# fx3.net
KiCad netlist of a schematic drawn in EAGLE
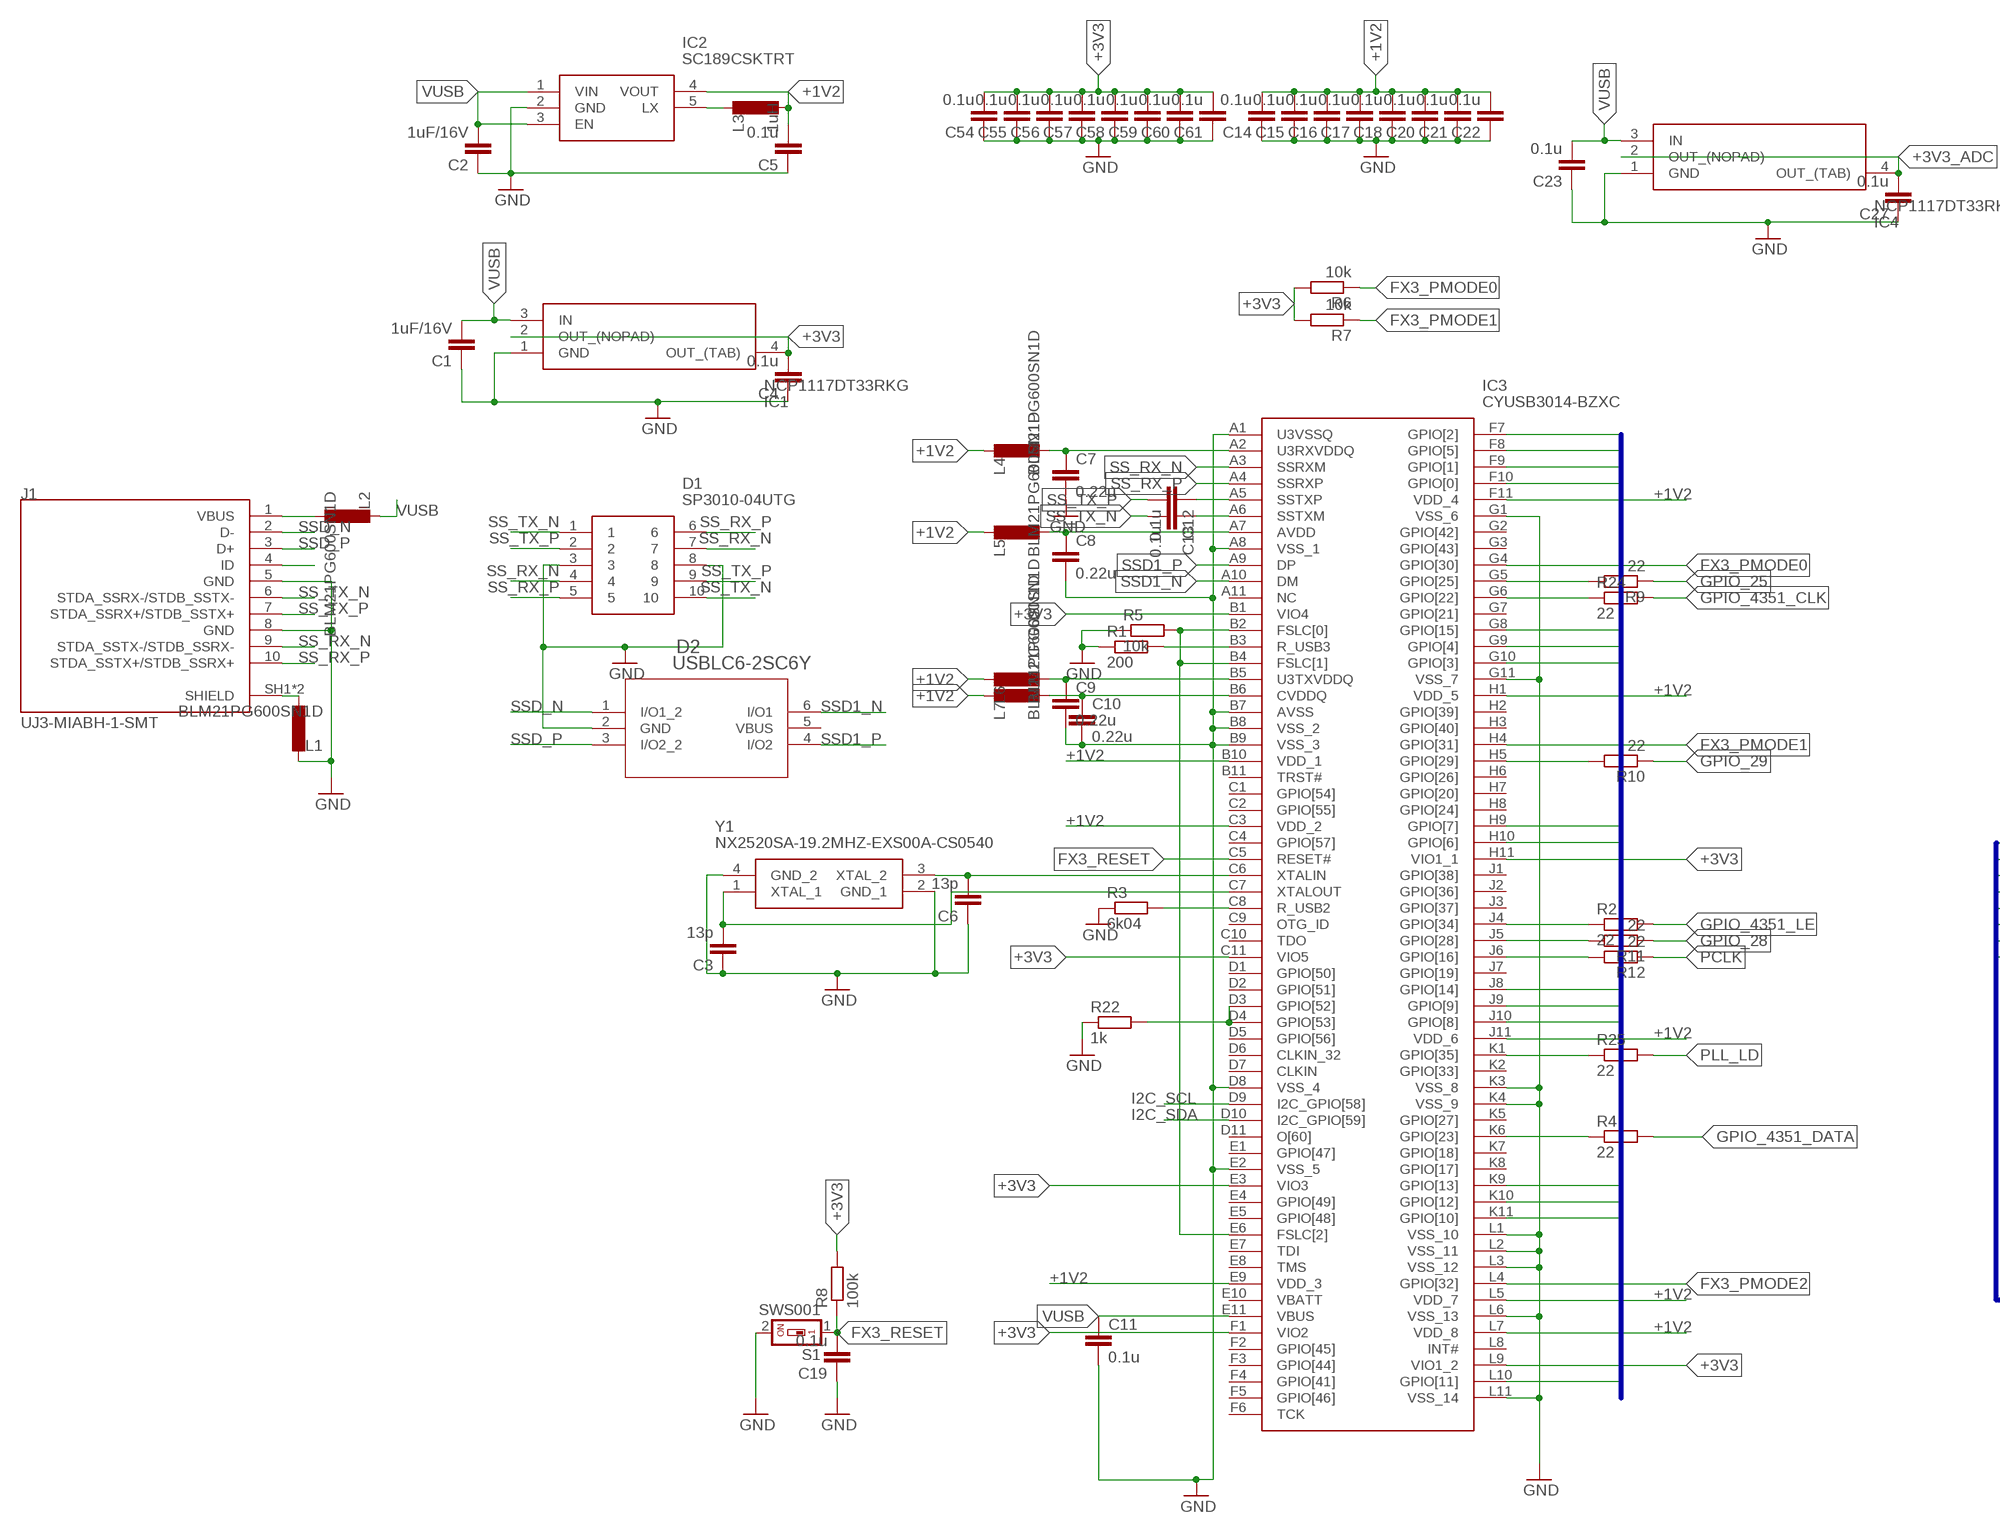
[diagram p0: schematic, sheet 1, part 1 of 2]
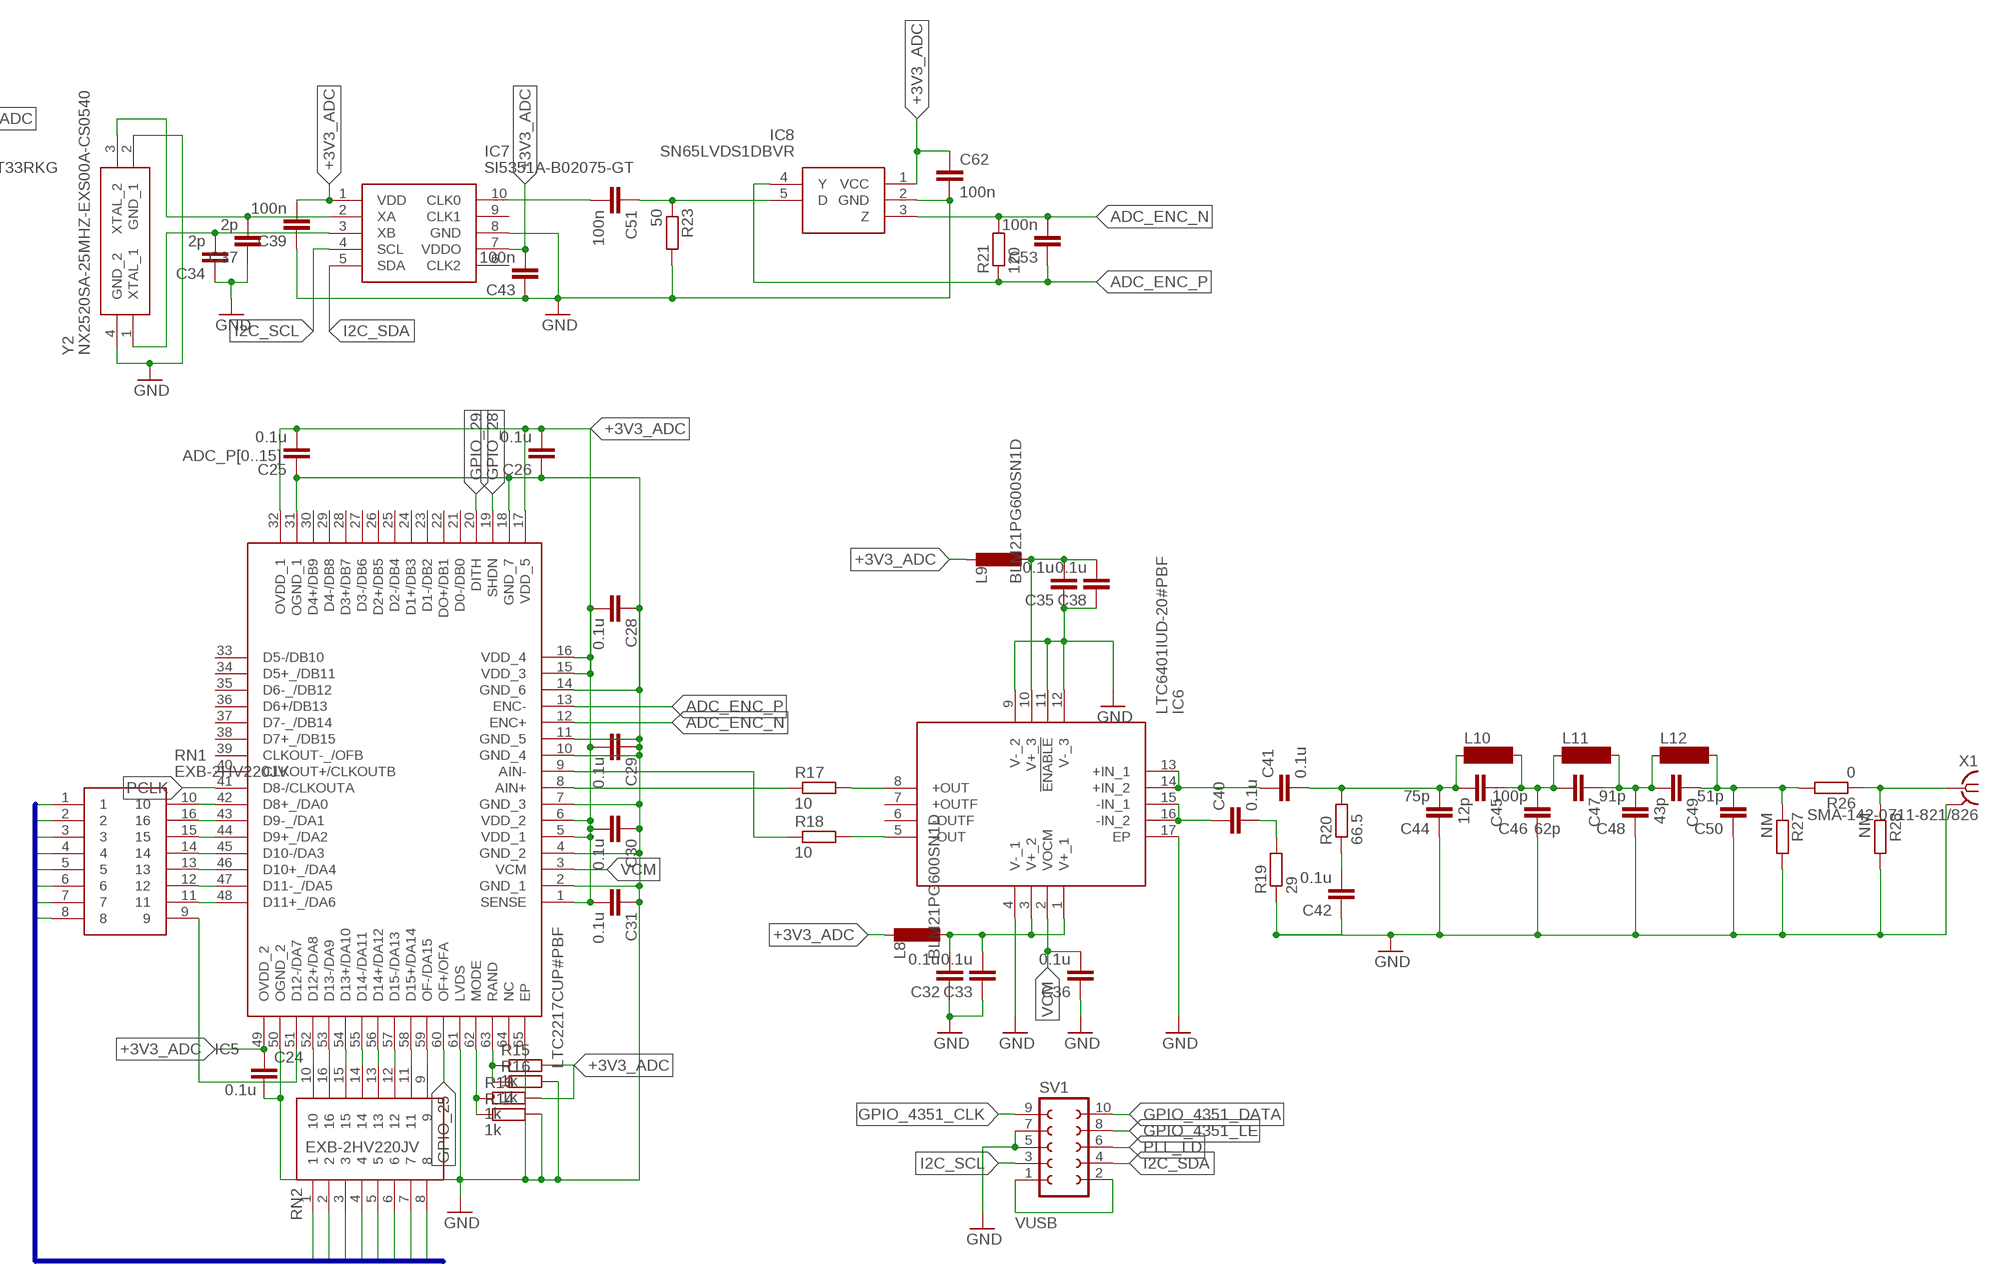
[diagram p1: schematic, sheet 1, part 2 of 2]

(export (version "E")
  (design (tool "Eeschema 10.0.6"))
  (components
    (comp (ref "C1")
      (value "1uF/16V")
      (footprint "eagle-import:C0603")
      (libsource (lib "eagle-import") (part "C-EUC0603"))
    )
    (comp (ref "C2")
      (value "1uF/16V")
      (footprint "eagle-import:C0603")
      (libsource (lib "eagle-import") (part "C-EUC0603"))
    )
    (comp (ref "C3")
      (value "13p")
      (footprint "eagle-import:C0603")
      (libsource (lib "eagle-import") (part "C-EUC0603"))
    )
    (comp (ref "C4")
      (value "0.1u")
      (footprint "eagle-import:C0603")
      (libsource (lib "eagle-import") (part "C-EUC0603"))
    )
    (comp (ref "C5")
      (value "0.1u")
      (footprint "eagle-import:C0603")
      (libsource (lib "eagle-import") (part "C-EUC0603"))
    )
    (comp (ref "C6")
      (value "13p")
      (footprint "eagle-import:C0603")
      (libsource (lib "eagle-import") (part "C-EUC0603"))
    )
    (comp (ref "C7")
      (value "0.22u")
      (footprint "eagle-import:C0603")
      (libsource (lib "eagle-import") (part "C-EUC0603"))
    )
    (comp (ref "C8")
      (value "0.22u")
      (footprint "eagle-import:C0603")
      (libsource (lib "eagle-import") (part "C-EUC0603"))
    )
    (comp (ref "C9")
      (value "0.22u")
      (footprint "eagle-import:C0603")
      (libsource (lib "eagle-import") (part "C-EUC0603"))
    )
    (comp (ref "C10")
      (value "0.22u")
      (footprint "eagle-import:C0603")
      (libsource (lib "eagle-import") (part "C-EUC0603"))
    )
    (comp (ref "C11")
      (value "0.1u")
      (footprint "eagle-import:C0603")
      (libsource (lib "eagle-import") (part "C-EUC0603"))
    )
    (comp (ref "C12")
      (value "0.1u")
      (footprint "eagle-import:C0603")
      (libsource (lib "eagle-import") (part "C-EUC0603"))
    )
    (comp (ref "C13")
      (value "0.1u")
      (footprint "eagle-import:C0603")
      (libsource (lib "eagle-import") (part "C-EUC0603"))
    )
    (comp (ref "C14")
      (value "0.1u")
      (footprint "eagle-import:C0603")
      (libsource (lib "eagle-import") (part "C-EUC0603"))
    )
    (comp (ref "C15")
      (value "0.1u")
      (footprint "eagle-import:C0603")
      (libsource (lib "eagle-import") (part "C-EUC0603"))
    )
    (comp (ref "C16")
      (value "0.1u")
      (footprint "eagle-import:C0603")
      (libsource (lib "eagle-import") (part "C-EUC0603"))
    )
    (comp (ref "C17")
      (value "0.1u")
      (footprint "eagle-import:C0603")
      (libsource (lib "eagle-import") (part "C-EUC0603"))
    )
    (comp (ref "C18")
      (value "0.1u")
      (footprint "eagle-import:C0603")
      (libsource (lib "eagle-import") (part "C-EUC0603"))
    )
    (comp (ref "C19")
      (value "0.1u")
      (footprint "eagle-import:C0603")
      (libsource (lib "eagle-import") (part "C-EUC0603"))
    )
    (comp (ref "C20")
      (value "0.1u")
      (footprint "eagle-import:C0603")
      (libsource (lib "eagle-import") (part "C-EUC0603"))
    )
    (comp (ref "C21")
      (value "0.1u")
      (footprint "eagle-import:C0603")
      (libsource (lib "eagle-import") (part "C-EUC0603"))
    )
    (comp (ref "C22")
      (value "0.1u")
      (footprint "eagle-import:C0603")
      (libsource (lib "eagle-import") (part "C-EUC0603"))
    )
    (comp (ref "C23")
      (value "0.1u")
      (footprint "eagle-import:C0603")
      (libsource (lib "eagle-import") (part "C-EUC0603"))
    )
    (comp (ref "C24")
      (value "0.1u")
      (footprint "eagle-import:C0603")
      (libsource (lib "eagle-import") (part "C-EUC0603"))
    )
    (comp (ref "C25")
      (value "0.1u")
      (footprint "eagle-import:C0603")
      (libsource (lib "eagle-import") (part "C-EUC0603"))
    )
    (comp (ref "C26")
      (value "0.1u")
      (footprint "eagle-import:C0603")
      (libsource (lib "eagle-import") (part "C-EUC0603"))
    )
    (comp (ref "C27")
      (value "0.1u")
      (footprint "eagle-import:C0603")
      (libsource (lib "eagle-import") (part "C-EUC0603"))
    )
    (comp (ref "C28")
      (value "0.1u")
      (footprint "eagle-import:C0603")
      (libsource (lib "eagle-import") (part "C-EUC0603"))
    )
    (comp (ref "C29")
      (value "0.1u")
      (footprint "eagle-import:C0603")
      (libsource (lib "eagle-import") (part "C-EUC0603"))
    )
    (comp (ref "C30")
      (value "0.1u")
      (footprint "eagle-import:C0603")
      (libsource (lib "eagle-import") (part "C-EUC0603"))
    )
    (comp (ref "C31")
      (value "0.1u")
      (footprint "eagle-import:C0603")
      (libsource (lib "eagle-import") (part "C-EUC0603"))
    )
    (comp (ref "C32")
      (value "0.1u")
      (footprint "eagle-import:C0603")
      (libsource (lib "eagle-import") (part "C-EUC0603"))
    )
    (comp (ref "C33")
      (value "0.1u")
      (footprint "eagle-import:C0603")
      (libsource (lib "eagle-import") (part "C-EUC0603"))
    )
    (comp (ref "C34")
      (value "2p")
      (footprint "eagle-import:C0603")
      (libsource (lib "eagle-import") (part "C-EUC0603"))
    )
    (comp (ref "C35")
      (value "0.1u")
      (footprint "eagle-import:C0603")
      (libsource (lib "eagle-import") (part "C-EUC0603"))
    )
    (comp (ref "C36")
      (value "0.1u")
      (footprint "eagle-import:C0603")
      (libsource (lib "eagle-import") (part "C-EUC0603"))
    )
    (comp (ref "C37")
      (value "2p")
      (footprint "eagle-import:C0603")
      (libsource (lib "eagle-import") (part "C-EUC0603"))
    )
    (comp (ref "C38")
      (value "0.1u")
      (footprint "eagle-import:C0603")
      (libsource (lib "eagle-import") (part "C-EUC0603"))
    )
    (comp (ref "C39")
      (value "100n")
      (footprint "eagle-import:C0603")
      (libsource (lib "eagle-import") (part "C-EUC0603"))
    )
    (comp (ref "C40")
      (value "0.1u")
      (footprint "eagle-import:C0603")
      (libsource (lib "eagle-import") (part "C-EUC0603"))
    )
    (comp (ref "C41")
      (value "0.1u")
      (footprint "eagle-import:C0603")
      (libsource (lib "eagle-import") (part "C-EUC0603"))
    )
    (comp (ref "C42")
      (value "0.1u")
      (footprint "eagle-import:C0603")
      (libsource (lib "eagle-import") (part "C-EUC0603"))
    )
    (comp (ref "C43")
      (value "100n")
      (footprint "eagle-import:C0603")
      (libsource (lib "eagle-import") (part "C-EUC0603"))
    )
    (comp (ref "C44")
      (value "75p")
      (footprint "eagle-import:C0603")
      (libsource (lib "eagle-import") (part "C-EUC0603"))
    )
    (comp (ref "C45")
      (value "12p")
      (footprint "eagle-import:C0603")
      (libsource (lib "eagle-import") (part "C-EUC0603"))
    )
    (comp (ref "C46")
      (value "100p")
      (footprint "eagle-import:C0603")
      (libsource (lib "eagle-import") (part "C-EUC0603"))
    )
    (comp (ref "C47")
      (value "62p")
      (footprint "eagle-import:C0603")
      (libsource (lib "eagle-import") (part "C-EUC0603"))
    )
    (comp (ref "C48")
      (value "91p")
      (footprint "eagle-import:C0603")
      (libsource (lib "eagle-import") (part "C-EUC0603"))
    )
    (comp (ref "C49")
      (value "43p")
      (footprint "eagle-import:C0603")
      (libsource (lib "eagle-import") (part "C-EUC0603"))
    )
    (comp (ref "C50")
      (value "51p")
      (footprint "eagle-import:C0603")
      (libsource (lib "eagle-import") (part "C-EUC0603"))
    )
    (comp (ref "C51")
      (value "100n")
      (footprint "eagle-import:C0603")
      (libsource (lib "eagle-import") (part "C-EUC0603"))
    )
    (comp (ref "C53")
      (value "100n")
      (footprint "eagle-import:C0603")
      (libsource (lib "eagle-import") (part "C-EUC0603"))
    )
    (comp (ref "C54")
      (value "0.1u")
      (footprint "eagle-import:C0603")
      (libsource (lib "eagle-import") (part "C-EUC0603"))
    )
    (comp (ref "C55")
      (value "0.1u")
      (footprint "eagle-import:C0603")
      (libsource (lib "eagle-import") (part "C-EUC0603"))
    )
    (comp (ref "C56")
      (value "0.1u")
      (footprint "eagle-import:C0603")
      (libsource (lib "eagle-import") (part "C-EUC0603"))
    )
    (comp (ref "C57")
      (value "0.1u")
      (footprint "eagle-import:C0603")
      (libsource (lib "eagle-import") (part "C-EUC0603"))
    )
    (comp (ref "C58")
      (value "0.1u")
      (footprint "eagle-import:C0603")
      (libsource (lib "eagle-import") (part "C-EUC0603"))
    )
    (comp (ref "C59")
      (value "0.1u")
      (footprint "eagle-import:C0603")
      (libsource (lib "eagle-import") (part "C-EUC0603"))
    )
    (comp (ref "C60")
      (value "0.1u")
      (footprint "eagle-import:C0603")
      (libsource (lib "eagle-import") (part "C-EUC0603"))
    )
    (comp (ref "C61")
      (value "0.1u")
      (footprint "eagle-import:C0603")
      (libsource (lib "eagle-import") (part "C-EUC0603"))
    )
    (comp (ref "C62")
      (value "100n")
      (footprint "eagle-import:C0603")
      (libsource (lib "eagle-import") (part "C-EUC0603"))
    )
    (comp (ref "D1")
      (value "SP3010-04UTG")
      (footprint "eagle-import:UDFN-10")
      (fields (field (name "MOUSER_PART_NUMBER") "576-SP3010-04UTG"))
      (libsource (lib "eagle-import") (part "SP3010-04UTG"))
    )
    (comp (ref "D2")
      (value "USBLC6-2SC6Y")
      (footprint "eagle-import:SOT23-6L_STM")
      (libsource (lib "eagle-import") (part "USBLC6-2SC6Y"))
    )
    (comp (ref "IC1")
      (value "NCP1117DT33RKG")
      (footprint "eagle-import:TO229P990X238-4N")
      (fields (field (name "MOUSER_PART_NUMBER") "863-NCP1117DT33RKG"))
      (libsource (lib "eagle-import") (part "NCP1117DT33RKG"))
    )
    (comp (ref "IC2")
      (value "SC189CSKTRT")
      (footprint "eagle-import:SOT95P280X145-5N")
      (fields (field (name "MOUSER_PART_NUMBER") "947-SC189CSKTRT"))
      (libsource (lib "eagle-import") (part "SC189CSKTRT"))
    )
    (comp (ref "IC3")
      (value "CYUSB3014-BZXC")
      (footprint "eagle-import:BGA121C80P11X11_1000X1000X120")
      (fields (field (name "MOUSER_PART_NUMBER") "727-CYUSB3014-BZXC"))
      (libsource (lib "eagle-import") (part "CYUSB3014-BZXC"))
    )
    (comp (ref "IC4")
      (value "NCP1117DT33RKG")
      (footprint "eagle-import:TO229P990X238-4N")
      (fields (field (name "MOUSER_PART_NUMBER") "863-NCP1117DT33RKG"))
      (libsource (lib "eagle-import") (part "NCP1117DT33RKG"))
    )
    (comp (ref "IC5")
      (value "LTC2217CUP#PBF")
      (footprint "eagle-import:QFN50P900X900X80-65N")
      (libsource (lib "eagle-import") (part "LTC2217CUP#PBF"))
    )
    (comp (ref "IC6")
      (value "LTC6401IUD-20#PBF")
      (footprint "eagle-import:QFN50P300X300X80-17N")
      (fields (field (name "MOUSER_PART_NUMBER") "584-LTC6401IUD-20PBF"))
      (libsource (lib "eagle-import") (part "LTC6401IUD-20#PBF"))
    )
    (comp (ref "IC7")
      (value "SI5351A-B02075-GT")
      (footprint "eagle-import:SOP50P490X110-10N")
      (fields
        (field (name "MANUFACTURER_PART_NUMBER") "Si5351A-B02075-GT")
        (field (name "MOUSER_PART_NUMBER") "634-SI5351A-B02075GT")
      )
      (libsource (lib "eagle-import") (part "SI5351A-B02075-GT"))
    )
    (comp (ref "IC8")
      (value "SN65LVDS1DBVR")
      (footprint "eagle-import:SOT95P280X145-5N")
      (fields (field (name "MOUSER_PART_NUMBER") "595-SN65LVDS1DBVR"))
      (libsource (lib "eagle-import") (part "SN65LVDS1DBVR"))
    )
    (comp (ref "J1")
      (value "UJ3-MIABH-1-SMT")
      (footprint "eagle-import:CUI_UJ3-MIABH-1-SMT")
      (fields (field (name "MF") "CUI Inc.") (field (name "MP") "UJ3-MIABH-1-SMT-TR"))
      (libsource (lib "eagle-import") (part "UJ3-MIABH-1-SMT"))
    )
    (comp (ref "L1")
      (value "BLM21PG600SN1D")
      (footprint "eagle-import:BLM21AG102BH1J")
      (fields (field (name "MOUSER_PART_NUMBER") "81-BLM21P600S"))
      (libsource (lib "eagle-import") (part "BLM21PG600SN1D"))
    )
    (comp (ref "L2")
      (value "BLM21PG600SN1D")
      (footprint "eagle-import:BLM21AG102BH1J")
      (fields (field (name "MOUSER_PART_NUMBER") "81-BLM21P600S"))
      (libsource (lib "eagle-import") (part "BLM21PG600SN1D"))
    )
    (comp (ref "L3")
      (value "1uH")
      (footprint "eagle-import:BLM21AG102BH1J")
      (fields
        (field (name "MANUFACTURER_PART_NUMBER") "BLM21PG600SN1D")
        (field (name "MOUSER_PART_NUMBER") "81-BLM21P600S")
      )
      (libsource (lib "eagle-import") (part "BLM21PG600SN1D"))
    )
    (comp (ref "L4")
      (value "BLM21PG600SN1D")
      (footprint "eagle-import:BLM21AG102BH1J")
      (fields (field (name "MOUSER_PART_NUMBER") "81-BLM21P600S"))
      (libsource (lib "eagle-import") (part "BLM21PG600SN1D"))
    )
    (comp (ref "L5")
      (value "BLM21PG600SN1D")
      (footprint "eagle-import:BLM21AG102BH1J")
      (fields (field (name "MOUSER_PART_NUMBER") "81-BLM21P600S"))
      (libsource (lib "eagle-import") (part "BLM21PG600SN1D"))
    )
    (comp (ref "L6")
      (value "BLM21PG600SN1D")
      (footprint "eagle-import:BLM21AG102BH1J")
      (fields (field (name "MOUSER_PART_NUMBER") "81-BLM21P600S"))
      (libsource (lib "eagle-import") (part "BLM21PG600SN1D"))
    )
    (comp (ref "L7")
      (value "BLM21PG600SN1D")
      (footprint "eagle-import:BLM21AG102BH1J")
      (fields (field (name "MOUSER_PART_NUMBER") "81-BLM21P600S"))
      (libsource (lib "eagle-import") (part "BLM21PG600SN1D"))
    )
    (comp (ref "L8")
      (value "BLM21PG600SN1D")
      (footprint "eagle-import:BLM21AG102BH1J")
      (fields (field (name "MOUSER_PART_NUMBER") "81-BLM21P600S"))
      (libsource (lib "eagle-import") (part "BLM21PG600SN1D"))
    )
    (comp (ref "L9")
      (value "BLM21PG600SN1D")
      (footprint "eagle-import:BLM21AG102BH1J")
      (fields (field (name "MOUSER_PART_NUMBER") "81-BLM21P600S"))
      (libsource (lib "eagle-import") (part "BLM21PG600SN1D"))
    )
    (comp (ref "L10")
      (value "MS85")
      (footprint "eagle-import:MS85")
      (libsource (lib "eagle-import") (part "MS85"))
    )
    (comp (ref "L11")
      (value "MS85")
      (footprint "eagle-import:MS85")
      (libsource (lib "eagle-import") (part "MS85"))
    )
    (comp (ref "L12")
      (value "MS85")
      (footprint "eagle-import:MS85")
      (libsource (lib "eagle-import") (part "MS85"))
    )
    (comp (ref "R1")
      (value "200")
      (footprint "eagle-import:R0603")
      (libsource (lib "eagle-import") (part "R-EU_R0603"))
    )
    (comp (ref "R2")
      (value "22")
      (footprint "eagle-import:R0603")
      (libsource (lib "eagle-import") (part "R-EU_R0603"))
    )
    (comp (ref "R3")
      (value "6k04")
      (footprint "eagle-import:R0603")
      (libsource (lib "eagle-import") (part "R-EU_R0603"))
    )
    (comp (ref "R4")
      (value "22")
      (footprint "eagle-import:R0603")
      (libsource (lib "eagle-import") (part "R-EU_R0603"))
    )
    (comp (ref "R5")
      (value "10k")
      (footprint "eagle-import:R0603")
      (libsource (lib "eagle-import") (part "R-EU_R0603"))
    )
    (comp (ref "R6")
      (value "10k")
      (footprint "eagle-import:R0603")
      (libsource (lib "eagle-import") (part "R-EU_R0603"))
    )
    (comp (ref "R7")
      (value "10k")
      (footprint "eagle-import:R0603")
      (libsource (lib "eagle-import") (part "R-EU_R0603"))
    )
    (comp (ref "R8")
      (value "100k")
      (footprint "eagle-import:R0603")
      (libsource (lib "eagle-import") (part "R-EU_R0603"))
    )
    (comp (ref "R9")
      (value "22")
      (footprint "eagle-import:R0603")
      (libsource (lib "eagle-import") (part "R-EU_R0603"))
    )
    (comp (ref "R10")
      (value "22")
      (footprint "eagle-import:R0603")
      (libsource (lib "eagle-import") (part "R-EU_R0603"))
    )
    (comp (ref "R11")
      (value "22")
      (footprint "eagle-import:R0603")
      (libsource (lib "eagle-import") (part "R-EU_R0603"))
    )
    (comp (ref "R12")
      (value "22")
      (footprint "eagle-import:R0603")
      (libsource (lib "eagle-import") (part "R-EU_R0603"))
    )
    (comp (ref "R13")
      (value "1k")
      (footprint "eagle-import:R0603")
      (libsource (lib "eagle-import") (part "R-EU_R0603"))
    )
    (comp (ref "R14")
      (value "1k")
      (footprint "eagle-import:R0603")
      (libsource (lib "eagle-import") (part "R-EU_R0603"))
    )
    (comp (ref "R15")
      (value "1k")
      (footprint "eagle-import:R0603")
      (libsource (lib "eagle-import") (part "R-EU_R0603"))
    )
    (comp (ref "R16")
      (value "1k")
      (footprint "eagle-import:R0603")
      (libsource (lib "eagle-import") (part "R-EU_R0603"))
    )
    (comp (ref "R17")
      (value "10")
      (footprint "eagle-import:R0603")
      (libsource (lib "eagle-import") (part "R-EU_R0603"))
    )
    (comp (ref "R18")
      (value "10")
      (footprint "eagle-import:R0603")
      (libsource (lib "eagle-import") (part "R-EU_R0603"))
    )
    (comp (ref "R19")
      (value "29")
      (footprint "eagle-import:R0603")
      (libsource (lib "eagle-import") (part "R-EU_R0603"))
    )
    (comp (ref "R20")
      (value "66.5")
      (footprint "eagle-import:R0603")
      (libsource (lib "eagle-import") (part "R-EU_R0603"))
    )
    (comp (ref "R21")
      (value "120")
      (footprint "eagle-import:R0603")
      (libsource (lib "eagle-import") (part "R-EU_R0603"))
    )
    (comp (ref "R22")
      (value "1k")
      (footprint "eagle-import:R0603")
      (libsource (lib "eagle-import") (part "R-EU_R0603"))
    )
    (comp (ref "R23")
      (value "50")
      (footprint "eagle-import:R0603")
      (libsource (lib "eagle-import") (part "R-EU_R0603"))
    )
    (comp (ref "R24")
      (value "22")
      (footprint "eagle-import:R0603")
      (libsource (lib "eagle-import") (part "R-EU_R0603"))
    )
    (comp (ref "R25")
      (value "22")
      (footprint "eagle-import:R0603")
      (libsource (lib "eagle-import") (part "R-EU_R0603"))
    )
    (comp (ref "R26")
      (value "0")
      (footprint "eagle-import:R0603")
      (libsource (lib "eagle-import") (part "R-EU_R0603"))
    )
    (comp (ref "R27")
      (value "NM")
      (footprint "eagle-import:R0603")
      (libsource (lib "eagle-import") (part "R-EU_R0603"))
    )
    (comp (ref "R28")
      (value "NM")
      (footprint "eagle-import:R0603")
      (libsource (lib "eagle-import") (part "R-EU_R0603"))
    )
    (comp (ref "RN1")
      (value "EXB-2HV220JV")
      (footprint "eagle-import:EXB2HV220JV")
      (fields (field (name "MOUSER_PART_NUMBER") "667-EXB-2HV220JV"))
      (libsource (lib "eagle-import") (part "EXB-2HV220JV"))
    )
    (comp (ref "RN2")
      (value "EXB-2HV220JV")
      (footprint "eagle-import:EXB2HV220JV")
      (fields (field (name "MOUSER_PART_NUMBER") "667-EXB-2HV220JV"))
      (libsource (lib "eagle-import") (part "EXB-2HV220JV"))
    )
    (comp (ref "S1")
      (value "SWS001")
      (footprint "eagle-import:SMS-001")
      (libsource (lib "eagle-import") (part "SWS001"))
    )
    (comp (ref "SV1")
      (value "FE05-2")
      (footprint "eagle-import:FE05-2")
      (libsource (lib "eagle-import") (part "FE05-2"))
    )
    (comp (ref "X1")
      (value "SMA-142-0711-821/826")
      (footprint "eagle-import:J502-ND-142-0711-821_826")
      (fields (field (name "MF") "JOHNSON COMPONENTS") (field (name "MPN") "142-0711-821"))
      (libsource (lib "eagle-import") (part "SMA-142-0711-821/826"))
    )
    (comp (ref "Y1")
      (value "NX2520SA-19.2MHZ-EXS00A-CS0540")
      (footprint "eagle-import:NX2520SA192MHZEXS00ACS05400")
      (fields
        (field (name "MANUFACTURER_PART_NUMBER") "NX2520SA-19.2MHz-EXS00A-CS05400")
        (field (name "MOUSER_PART_NUMBER") "344-NX2520SA19.2MH54")
      )
      (libsource (lib "eagle-import") (part "NX2520SA-19.2MHZ-EXS00A-CS0540"))
    )
    (comp (ref "Y2")
      (value "NX2520SA-25MHZ-EXS00A-CS0540")
      (footprint "eagle-import:NX2520SA192MHZEXS00ACS05400")
      (fields
        (field (name "MANUFACTURER_PART_NUMBER") "NX2520SA-19.2MHz-EXS00A-CS05400")
        (field (name "MOUSER_PART_NUMBER") "344-NX2520SA19.2MH54")
      )
      (libsource (lib "eagle-import") (part "NX2520SA-19.2MHZ-EXS00A-CS0540"))
    )
  )
  (nets
    (net (code "1") (name "+1V2") (class "Default")
      (node (ref "C14") (pin "2") (pinfunction "2_2") (pintype "passive"))
      (node (ref "C15") (pin "2") (pinfunction "2_2") (pintype "passive"))
      (node (ref "C16") (pin "2") (pinfunction "2_2") (pintype "passive"))
      (node (ref "C17") (pin "2") (pinfunction "2_2") (pintype "passive"))
      (node (ref "C18") (pin "2") (pinfunction "2_2") (pintype "passive"))
      (node (ref "C20") (pin "2") (pinfunction "2_2") (pintype "passive"))
      (node (ref "C21") (pin "2") (pinfunction "2_2") (pintype "passive"))
      (node (ref "C22") (pin "2") (pinfunction "2_2") (pintype "passive"))
      (node (ref "C5") (pin "2") (pinfunction "2_2") (pintype "passive"))
      (node (ref "IC2") (pin "4") (pinfunction "VOUT_4") (pintype "bidirectional"))
      (node (ref "IC3") (pin "B10") (pinfunction "VDD_1_B10") (pintype "bidirectional"))
      (node (ref "IC3") (pin "C3") (pinfunction "VDD_2_C3") (pintype "bidirectional"))
      (node (ref "IC3") (pin "E9") (pinfunction "VDD_3_E9") (pintype "bidirectional"))
      (node (ref "IC3") (pin "F11") (pinfunction "VDD_4_F11") (pintype "bidirectional"))
      (node (ref "IC3") (pin "H1") (pinfunction "VDD_5_H1") (pintype "bidirectional"))
      (node (ref "IC3") (pin "J11") (pinfunction "VDD_6_J11") (pintype "bidirectional"))
      (node (ref "IC3") (pin "L5") (pinfunction "VDD_7_L5") (pintype "bidirectional"))
      (node (ref "IC3") (pin "L7") (pinfunction "VDD_8_L7") (pintype "bidirectional"))
      (node (ref "L3") (pin "2") (pinfunction "2_2") (pintype "passive"))
      (node (ref "L4") (pin "1") (pinfunction "1_1") (pintype "passive"))
      (node (ref "L5") (pin "1") (pinfunction "1_1") (pintype "passive"))
      (node (ref "L6") (pin "1") (pinfunction "1_1") (pintype "passive"))
      (node (ref "L7") (pin "1") (pinfunction "1_1") (pintype "passive"))
    )
    (net (code "2") (name "+3V3") (class "Default")
      (node (ref "C4") (pin "2") (pinfunction "2_2") (pintype "passive"))
      (node (ref "C54") (pin "2") (pinfunction "2_2") (pintype "passive"))
      (node (ref "C55") (pin "2") (pinfunction "2_2") (pintype "passive"))
      (node (ref "C56") (pin "2") (pinfunction "2_2") (pintype "passive"))
      (node (ref "C57") (pin "2") (pinfunction "2_2") (pintype "passive"))
      (node (ref "C58") (pin "2") (pinfunction "2_2") (pintype "passive"))
      (node (ref "C59") (pin "2") (pinfunction "2_2") (pintype "passive"))
      (node (ref "C60") (pin "2") (pinfunction "2_2") (pintype "passive"))
      (node (ref "C61") (pin "2") (pinfunction "2_2") (pintype "passive"))
      (node (ref "IC1") (pin "2") (pinfunction "OUT_(NOPAD)_2") (pintype "output"))
      (node (ref "IC1") (pin "4") (pinfunction "OUT_(TAB)_4") (pintype "output"))
      (node (ref "IC3") (pin "B1") (pinfunction "VIO4_B1") (pintype "bidirectional"))
      (node (ref "IC3") (pin "C11") (pinfunction "VIO5_C11") (pintype "bidirectional"))
      (node (ref "IC3") (pin "E3") (pinfunction "VIO3_E3") (pintype "bidirectional"))
      (node (ref "IC3") (pin "F1") (pinfunction "VIO2_F1") (pintype "bidirectional"))
      (node (ref "IC3") (pin "H11") (pinfunction "VIO1_1_H11") (pintype "bidirectional"))
      (node (ref "IC3") (pin "L9") (pinfunction "VIO1_2_L9") (pintype "bidirectional"))
      (node (ref "R6") (pin "2") (pinfunction "2_2") (pintype "passive"))
      (node (ref "R7") (pin "2") (pinfunction "2_2") (pintype "passive"))
      (node (ref "R8") (pin "2") (pinfunction "2_2") (pintype "passive"))
    )
    (net (code "3") (name "+3V3_ADC") (class "Default")
      (node (ref "C24") (pin "1") (pinfunction "1_1") (pintype "passive"))
      (node (ref "C25") (pin "2") (pinfunction "2_2") (pintype "passive"))
      (node (ref "C26") (pin "2") (pinfunction "2_2") (pintype "passive"))
      (node (ref "C27") (pin "2") (pinfunction "2_2") (pintype "passive"))
      (node (ref "C28") (pin "2") (pinfunction "2_2") (pintype "passive"))
      (node (ref "C29") (pin "2") (pinfunction "2_2") (pintype "passive"))
      (node (ref "C30") (pin "2") (pinfunction "2_2") (pintype "passive"))
      (node (ref "C31") (pin "2") (pinfunction "2_2") (pintype "passive"))
      (node (ref "C39") (pin "2") (pinfunction "2_2") (pintype "passive"))
      (node (ref "C43") (pin "2") (pinfunction "2_2") (pintype "passive"))
      (node (ref "C62") (pin "1") (pinfunction "1_1") (pintype "passive"))
      (node (ref "IC4") (pin "2") (pinfunction "OUT_(NOPAD)_2") (pintype "output"))
      (node (ref "IC4") (pin "4") (pinfunction "OUT_(TAB)_4") (pintype "output"))
      (node (ref "IC5") (pin "1") (pinfunction "SENSE_1") (pintype "bidirectional"))
      (node (ref "IC5") (pin "15") (pinfunction "VDD_3_15") (pintype "bidirectional"))
      (node (ref "IC5") (pin "16") (pinfunction "VDD_4_16") (pintype "bidirectional"))
      (node (ref "IC5") (pin "17") (pinfunction "VDD_5_17") (pintype "bidirectional"))
      (node (ref "IC5") (pin "32") (pinfunction "OVDD_1_32") (pintype "bidirectional"))
      (node (ref "IC5") (pin "49") (pinfunction "OVDD_2_49") (pintype "bidirectional"))
      (node (ref "IC5") (pin "5") (pinfunction "VDD_1_5") (pintype "bidirectional"))
      (node (ref "IC5") (pin "6") (pinfunction "VDD_2_6") (pintype "bidirectional"))
      (node (ref "IC7") (pin "1") (pinfunction "VDD_1") (pintype "bidirectional"))
      (node (ref "IC7") (pin "7") (pinfunction "VDDO_7") (pintype "bidirectional"))
      (node (ref "IC8") (pin "1") (pinfunction "VCC_1") (pintype "power_in"))
      (node (ref "L8") (pin "1") (pinfunction "1_1") (pintype "passive"))
      (node (ref "L9") (pin "1") (pinfunction "1_1") (pintype "passive"))
      (node (ref "R13") (pin "2") (pinfunction "2_2") (pintype "passive"))
      (node (ref "R15") (pin "2") (pinfunction "2_2") (pintype "passive"))
    )
    (net (code "5") (name "ADC_ENC_N") (class "Default")
      (node (ref "C53") (pin "2") (pinfunction "2_2") (pintype "passive"))
      (node (ref "IC5") (pin "12") (pinfunction "ENC+_12") (pintype "bidirectional"))
      (node (ref "IC8") (pin "3") (pinfunction "Z_3") (pintype "bidirectional"))
      (node (ref "R21") (pin "2") (pinfunction "2_2") (pintype "passive"))
    )
    (net (code "6") (name "ADC_ENC_P") (class "Default")
      (node (ref "C53") (pin "1") (pinfunction "1_1") (pintype "passive"))
      (node (ref "IC5") (pin "13") (pinfunction "ENC-_13") (pintype "bidirectional"))
      (node (ref "IC8") (pin "4") (pinfunction "Y_4") (pintype "bidirectional"))
      (node (ref "R21") (pin "1") (pinfunction "1_1") (pintype "passive"))
    )
    (net (code "7") (name "ADC_P0") (class "Default")
      (node (ref "IC3") (pin "F10") (pinfunction "GPIO[0]_F10") (pintype "bidirectional"))
      (node (ref "RN1") (pin "1") (pinfunction "1_1") (pintype "bidirectional"))
    )
    (net (code "8") (name "ADC_P1") (class "Default")
      (node (ref "IC3") (pin "F9") (pinfunction "GPIO[1]_F9") (pintype "bidirectional"))
      (node (ref "RN1") (pin "2") (pinfunction "2_2") (pintype "bidirectional"))
    )
    (net (code "9") (name "ADC_P2") (class "Default")
      (node (ref "IC3") (pin "F7") (pinfunction "GPIO[2]_F7") (pintype "bidirectional"))
      (node (ref "RN1") (pin "3") (pinfunction "3_3") (pintype "bidirectional"))
    )
    (net (code "10") (name "ADC_P3") (class "Default")
      (node (ref "IC3") (pin "G10") (pinfunction "GPIO[3]_G10") (pintype "bidirectional"))
      (node (ref "RN1") (pin "4") (pinfunction "4_4") (pintype "bidirectional"))
    )
    (net (code "11") (name "ADC_P4") (class "Default")
      (node (ref "IC3") (pin "G9") (pinfunction "GPIO[4]_G9") (pintype "bidirectional"))
      (node (ref "RN1") (pin "5") (pinfunction "5_5") (pintype "bidirectional"))
    )
    (net (code "12") (name "ADC_P5") (class "Default")
      (node (ref "IC3") (pin "F8") (pinfunction "GPIO[5]_F8") (pintype "bidirectional"))
      (node (ref "RN1") (pin "6") (pinfunction "6_6") (pintype "bidirectional"))
    )
    (net (code "13") (name "ADC_P6") (class "Default")
      (node (ref "IC3") (pin "H10") (pinfunction "GPIO[6]_H10") (pintype "bidirectional"))
      (node (ref "RN1") (pin "7") (pinfunction "7_7") (pintype "bidirectional"))
    )
    (net (code "14") (name "ADC_P7") (class "Default")
      (node (ref "IC3") (pin "H9") (pinfunction "GPIO[7]_H9") (pintype "bidirectional"))
      (node (ref "RN1") (pin "8") (pinfunction "8_8") (pintype "bidirectional"))
    )
    (net (code "15") (name "ADC_P8") (class "Default")
      (node (ref "IC3") (pin "J10") (pinfunction "GPIO[8]_J10") (pintype "bidirectional"))
      (node (ref "RN2") (pin "1") (pinfunction "1_1") (pintype "bidirectional"))
    )
    (net (code "16") (name "ADC_P9") (class "Default")
      (node (ref "IC3") (pin "J9") (pinfunction "GPIO[9]_J9") (pintype "bidirectional"))
      (node (ref "RN2") (pin "2") (pinfunction "2_2") (pintype "bidirectional"))
    )
    (net (code "17") (name "ADC_P10") (class "Default")
      (node (ref "IC3") (pin "K11") (pinfunction "GPIO[10]_K11") (pintype "bidirectional"))
      (node (ref "RN2") (pin "3") (pinfunction "3_3") (pintype "bidirectional"))
    )
    (net (code "18") (name "ADC_P11") (class "Default")
      (node (ref "IC3") (pin "L10") (pinfunction "GPIO[11]_L10") (pintype "bidirectional"))
      (node (ref "RN2") (pin "4") (pinfunction "4_4") (pintype "bidirectional"))
    )
    (net (code "19") (name "ADC_P12") (class "Default")
      (node (ref "IC3") (pin "K10") (pinfunction "GPIO[12]_K10") (pintype "bidirectional"))
      (node (ref "RN2") (pin "5") (pinfunction "5_5") (pintype "bidirectional"))
    )
    (net (code "20") (name "ADC_P13") (class "Default")
      (node (ref "IC3") (pin "K9") (pinfunction "GPIO[13]_K9") (pintype "bidirectional"))
      (node (ref "RN2") (pin "6") (pinfunction "6_6") (pintype "bidirectional"))
    )
    (net (code "21") (name "ADC_P14") (class "Default")
      (node (ref "IC3") (pin "J8") (pinfunction "GPIO[14]_J8") (pintype "bidirectional"))
      (node (ref "RN2") (pin "7") (pinfunction "7_7") (pintype "bidirectional"))
    )
    (net (code "22") (name "ADC_P15") (class "Default")
      (node (ref "IC3") (pin "G8") (pinfunction "GPIO[15]_G8") (pintype "bidirectional"))
      (node (ref "RN2") (pin "8") (pinfunction "8_8") (pintype "bidirectional"))
    )
    (net (code "23") (name "FX3_PMODE0") (class "Default")
      (node (ref "IC3") (pin "G4") (pinfunction "GPIO[30]_G4") (pintype "bidirectional"))
      (node (ref "R6") (pin "1") (pinfunction "1_1") (pintype "passive"))
    )
    (net (code "24") (name "FX3_PMODE1") (class "Default")
      (node (ref "IC3") (pin "H4") (pinfunction "GPIO[31]_H4") (pintype "bidirectional"))
      (node (ref "R7") (pin "1") (pinfunction "1_1") (pintype "passive"))
    )
    (net (code "25") (name "FX3_PMODE2") (class "Default")
      (node (ref "IC3") (pin "L4") (pinfunction "GPIO[32]_L4") (pintype "bidirectional"))
    )
    (net (code "26") (name "FX3_RESET") (class "Default")
      (node (ref "C19") (pin "2") (pinfunction "2_2") (pintype "passive"))
      (node (ref "IC3") (pin "C5") (pinfunction "RESET#_C5") (pintype "bidirectional"))
      (node (ref "R8") (pin "1") (pinfunction "1_1") (pintype "passive"))
      (node (ref "S1") (pin "1") (pinfunction "1_1") (pintype "passive"))
    )
    (net (code "27") (name "GND") (class "Default")
      (node (ref "C1") (pin "1") (pinfunction "1_1") (pintype "passive"))
      (node (ref "C10") (pin "2") (pinfunction "2_2") (pintype "passive"))
      (node (ref "C11") (pin "2") (pinfunction "2_2") (pintype "passive"))
      (node (ref "C14") (pin "1") (pinfunction "1_1") (pintype "passive"))
      (node (ref "C15") (pin "1") (pinfunction "1_1") (pintype "passive"))
      (node (ref "C16") (pin "1") (pinfunction "1_1") (pintype "passive"))
      (node (ref "C17") (pin "1") (pinfunction "1_1") (pintype "passive"))
      (node (ref "C18") (pin "1") (pinfunction "1_1") (pintype "passive"))
      (node (ref "C19") (pin "1") (pinfunction "1_1") (pintype "passive"))
      (node (ref "C2") (pin "1") (pinfunction "1_1") (pintype "passive"))
      (node (ref "C20") (pin "1") (pinfunction "1_1") (pintype "passive"))
      (node (ref "C21") (pin "1") (pinfunction "1_1") (pintype "passive"))
      (node (ref "C22") (pin "1") (pinfunction "1_1") (pintype "passive"))
      (node (ref "C23") (pin "1") (pinfunction "1_1") (pintype "passive"))
      (node (ref "C24") (pin "2") (pinfunction "2_2") (pintype "passive"))
      (node (ref "C25") (pin "1") (pinfunction "1_1") (pintype "passive"))
      (node (ref "C26") (pin "1") (pinfunction "1_1") (pintype "passive"))
      (node (ref "C27") (pin "1") (pinfunction "1_1") (pintype "passive"))
      (node (ref "C28") (pin "1") (pinfunction "1_1") (pintype "passive"))
      (node (ref "C29") (pin "1") (pinfunction "1_1") (pintype "passive"))
      (node (ref "C3") (pin "1") (pinfunction "1_1") (pintype "passive"))
      (node (ref "C30") (pin "1") (pinfunction "1_1") (pintype "passive"))
      (node (ref "C31") (pin "1") (pinfunction "1_1") (pintype "passive"))
      (node (ref "C32") (pin "1") (pinfunction "1_1") (pintype "passive"))
      (node (ref "C33") (pin "1") (pinfunction "1_1") (pintype "passive"))
      (node (ref "C34") (pin "1") (pinfunction "1_1") (pintype "passive"))
      (node (ref "C35") (pin "1") (pinfunction "1_1") (pintype "passive"))
      (node (ref "C36") (pin "1") (pinfunction "1_1") (pintype "passive"))
      (node (ref "C37") (pin "1") (pinfunction "1_1") (pintype "passive"))
      (node (ref "C38") (pin "1") (pinfunction "1_1") (pintype "passive"))
      (node (ref "C39") (pin "1") (pinfunction "1_1") (pintype "passive"))
      (node (ref "C4") (pin "1") (pinfunction "1_1") (pintype "passive"))
      (node (ref "C42") (pin "1") (pinfunction "1_1") (pintype "passive"))
      (node (ref "C43") (pin "1") (pinfunction "1_1") (pintype "passive"))
      (node (ref "C44") (pin "1") (pinfunction "1_1") (pintype "passive"))
      (node (ref "C46") (pin "1") (pinfunction "1_1") (pintype "passive"))
      (node (ref "C48") (pin "1") (pinfunction "1_1") (pintype "passive"))
      (node (ref "C5") (pin "1") (pinfunction "1_1") (pintype "passive"))
      (node (ref "C50") (pin "1") (pinfunction "1_1") (pintype "passive"))
      (node (ref "C54") (pin "1") (pinfunction "1_1") (pintype "passive"))
      (node (ref "C55") (pin "1") (pinfunction "1_1") (pintype "passive"))
      (node (ref "C56") (pin "1") (pinfunction "1_1") (pintype "passive"))
      (node (ref "C57") (pin "1") (pinfunction "1_1") (pintype "passive"))
      (node (ref "C58") (pin "1") (pinfunction "1_1") (pintype "passive"))
      (node (ref "C59") (pin "1") (pinfunction "1_1") (pintype "passive"))
      (node (ref "C6") (pin "1") (pinfunction "1_1") (pintype "passive"))
      (node (ref "C60") (pin "1") (pinfunction "1_1") (pintype "passive"))
      (node (ref "C61") (pin "1") (pinfunction "1_1") (pintype "passive"))
      (node (ref "C62") (pin "2") (pinfunction "2_2") (pintype "passive"))
      (node (ref "C7") (pin "2") (pinfunction "2_2") (pintype "passive"))
      (node (ref "C8") (pin "2") (pinfunction "2_2") (pintype "passive"))
      (node (ref "C9") (pin "2") (pinfunction "2_2") (pintype "passive"))
      (node (ref "D1") (pin "3") (pinfunction "3_3") (pintype "bidirectional"))
      (node (ref "D1") (pin "8") (pinfunction "8_8") (pintype "bidirectional"))
      (node (ref "D2") (pin "2") (pinfunction "GND_2") (pintype "power_in"))
      (node (ref "IC1") (pin "1") (pinfunction "GND_1") (pintype "power_in"))
      (node (ref "IC2") (pin "2") (pinfunction "GND_2") (pintype "bidirectional"))
      (node (ref "IC3") (pin "A1") (pinfunction "U3VSSQ_A1") (pintype "bidirectional"))
      (node (ref "IC3") (pin "A8") (pinfunction "VSS_1_A8") (pintype "bidirectional"))
      (node (ref "IC3") (pin "B7") (pinfunction "AVSS_B7") (pintype "bidirectional"))
      (node (ref "IC3") (pin "B8") (pinfunction "VSS_2_B8") (pintype "bidirectional"))
      (node (ref "IC3") (pin "B9") (pinfunction "VSS_3_B9") (pintype "bidirectional"))
      (node (ref "IC3") (pin "D8") (pinfunction "VSS_4_D8") (pintype "bidirectional"))
      (node (ref "IC3") (pin "E2") (pinfunction "VSS_5_E2") (pintype "bidirectional"))
      (node (ref "IC3") (pin "G1") (pinfunction "VSS_6_G1") (pintype "bidirectional"))
      (node (ref "IC3") (pin "G11") (pinfunction "VSS_7_G11") (pintype "bidirectional"))
      (node (ref "IC3") (pin "K3") (pinfunction "VSS_8_K3") (pintype "bidirectional"))
      (node (ref "IC3") (pin "K4") (pinfunction "VSS_9_K4") (pintype "bidirectional"))
      (node (ref "IC3") (pin "L1") (pinfunction "VSS_10_L1") (pintype "bidirectional"))
      (node (ref "IC3") (pin "L11") (pinfunction "VSS_14_L11") (pintype "bidirectional"))
      (node (ref "IC3") (pin "L2") (pinfunction "VSS_11_L2") (pintype "bidirectional"))
      (node (ref "IC3") (pin "L3") (pinfunction "VSS_12_L3") (pintype "bidirectional"))
      (node (ref "IC3") (pin "L6") (pinfunction "VSS_13_L6") (pintype "bidirectional"))
      (node (ref "IC4") (pin "1") (pinfunction "GND_1") (pintype "power_in"))
      (node (ref "IC5") (pin "10") (pinfunction "GND_4_10") (pintype "bidirectional"))
      (node (ref "IC5") (pin "11") (pinfunction "GND_5_11") (pintype "bidirectional"))
      (node (ref "IC5") (pin "14") (pinfunction "GND_6_14") (pintype "bidirectional"))
      (node (ref "IC5") (pin "18") (pinfunction "GND_7_18") (pintype "bidirectional"))
      (node (ref "IC5") (pin "2") (pinfunction "GND_1_2") (pintype "bidirectional"))
      (node (ref "IC5") (pin "31") (pinfunction "OGND_1_31") (pintype "bidirectional"))
      (node (ref "IC5") (pin "4") (pinfunction "GND_2_4") (pintype "bidirectional"))
      (node (ref "IC5") (pin "50") (pinfunction "OGND_2_50") (pintype "bidirectional"))
      (node (ref "IC5") (pin "61") (pinfunction "LVDS_61") (pintype "bidirectional"))
      (node (ref "IC5") (pin "65") (pinfunction "EP_65") (pintype "bidirectional"))
      (node (ref "IC5") (pin "7") (pinfunction "GND_3_7") (pintype "bidirectional"))
      (node (ref "IC6") (pin "11") (pinfunction "~{ENABLE}_11") (pintype "bidirectional"))
      (node (ref "IC6") (pin "12") (pinfunction "V-_3_12") (pintype "bidirectional"))
      (node (ref "IC6") (pin "17") (pinfunction "EP_17") (pintype "bidirectional"))
      (node (ref "IC6") (pin "4") (pinfunction "V-_1_4") (pintype "bidirectional"))
      (node (ref "IC6") (pin "9") (pinfunction "V-_2_9") (pintype "bidirectional"))
      (node (ref "IC7") (pin "8") (pinfunction "GND_8") (pintype "bidirectional"))
      (node (ref "IC8") (pin "2") (pinfunction "GND_2") (pintype "power_in"))
      (node (ref "J1") (pin "5") (pinfunction "GND_5") (pintype "power_in"))
      (node (ref "J1") (pin "8") (pinfunction "GND_8") (pintype "power_in"))
      (node (ref "L1") (pin "1") (pinfunction "1_1") (pintype "passive"))
      (node (ref "R1") (pin "1") (pinfunction "1_1") (pintype "passive"))
      (node (ref "R14") (pin "2") (pinfunction "2_2") (pintype "passive"))
      (node (ref "R16") (pin "2") (pinfunction "2_2") (pintype "passive"))
      (node (ref "R19") (pin "1") (pinfunction "1_1") (pintype "passive"))
      (node (ref "R22") (pin "1") (pinfunction "1_1") (pintype "passive"))
      (node (ref "R23") (pin "2") (pinfunction "2_2") (pintype "passive"))
      (node (ref "R27") (pin "2") (pinfunction "2_2") (pintype "passive"))
      (node (ref "R28") (pin "2") (pinfunction "2_2") (pintype "passive"))
      (node (ref "R3") (pin "1") (pinfunction "1_1") (pintype "passive"))
      (node (ref "R5") (pin "1") (pinfunction "1_1") (pintype "passive"))
      (node (ref "S1") (pin "2") (pinfunction "2_2") (pintype "passive"))
      (node (ref "SV1") (pin "5") (pinfunction "5_5") (pintype "passive"))
      (node (ref "SV1") (pin "7") (pinfunction "7_7") (pintype "passive"))
      (node (ref "X1") (pin "G@1") (pinfunction "2_G@1") (pintype "passive"))
      (node (ref "X1") (pin "G@2") (pinfunction "2_G@2") (pintype "passive"))
      (node (ref "X1") (pin "G@3") (pinfunction "2_G@3") (pintype "passive"))
      (node (ref "X1") (pin "G@4") (pinfunction "2_G@4") (pintype "passive"))
      (node (ref "Y1") (pin "2") (pinfunction "GND_1_2") (pintype "bidirectional"))
      (node (ref "Y1") (pin "4") (pinfunction "GND_2_4") (pintype "bidirectional"))
      (node (ref "Y2") (pin "2") (pinfunction "GND_1_2") (pintype "bidirectional"))
      (node (ref "Y2") (pin "4") (pinfunction "GND_2_4") (pintype "bidirectional"))
    )
    (net (code "28") (name "GPIO_25") (class "Default")
      (node (ref "IC5") (pin "60") (pinfunction "OF+/OFA_60") (pintype "bidirectional"))
      (node (ref "R9") (pin "1") (pinfunction "1_1") (pintype "passive"))
    )
    (net (code "29") (name "GPIO_28") (class "Default")
      (node (ref "IC5") (pin "19") (pinfunction "SHDN_19") (pintype "bidirectional"))
      (node (ref "R11") (pin "1") (pinfunction "1_1") (pintype "passive"))
    )
    (net (code "30") (name "GPIO_29") (class "Default")
      (node (ref "IC5") (pin "20") (pinfunction "DITH_20") (pintype "bidirectional"))
      (node (ref "R10") (pin "1") (pinfunction "1_1") (pintype "passive"))
    )
    (net (code "31") (name "GPIO_4351_CLK") (class "Default")
      (node (ref "R24") (pin "2") (pinfunction "2_2") (pintype "passive"))
      (node (ref "SV1") (pin "9") (pinfunction "9_9") (pintype "passive"))
    )
    (net (code "32") (name "GPIO_4351_DATA") (class "Default")
      (node (ref "R4") (pin "2") (pinfunction "2_2") (pintype "passive"))
      (node (ref "SV1") (pin "10") (pinfunction "10_10") (pintype "passive"))
    )
    (net (code "33") (name "GPIO_4351_LE") (class "Default")
      (node (ref "R2") (pin "2") (pinfunction "2_2") (pintype "passive"))
      (node (ref "SV1") (pin "8") (pinfunction "8_8") (pintype "passive"))
    )
    (net (code "34") (name "I2C_SCL") (class "Default")
      (node (ref "IC3") (pin "D9") (pinfunction "I2C_GPIO[58]_D9") (pintype "bidirectional"))
      (node (ref "IC7") (pin "4") (pinfunction "SCL_4") (pintype "bidirectional"))
      (node (ref "SV1") (pin "3") (pinfunction "3_3") (pintype "passive"))
    )
    (net (code "35") (name "I2C_SDA") (class "Default")
      (node (ref "IC3") (pin "D10") (pinfunction "I2C_GPIO[59]_D10") (pintype "bidirectional"))
      (node (ref "IC7") (pin "5") (pinfunction "SDA_5") (pintype "bidirectional"))
      (node (ref "SV1") (pin "4") (pinfunction "4_4") (pintype "passive"))
    )
    (net (code "36") (name "Net-(C40-Pad2)") (class "Default")
      (node (ref "C40") (pin "2") (pinfunction "2_2") (pintype "passive"))
      (node (ref "R19") (pin "2") (pinfunction "2_2") (pintype "passive"))
    )
    (net (code "37") (name "Net-(C41-Pad2)") (class "Default")
      (node (ref "C41") (pin "2") (pinfunction "2_2") (pintype "passive"))
      (node (ref "C44") (pin "2") (pinfunction "2_2") (pintype "passive"))
      (node (ref "C45") (pin "2") (pinfunction "2_2") (pintype "passive"))
      (node (ref "L10") (pin "1") (pinfunction "1_1") (pintype "passive"))
      (node (ref "R20") (pin "2") (pinfunction "2_2") (pintype "passive"))
    )
    (net (code "38") (name "Net-(C42-Pad2)") (class "Default")
      (node (ref "C42") (pin "2") (pinfunction "2_2") (pintype "passive"))
      (node (ref "R20") (pin "1") (pinfunction "1_1") (pintype "passive"))
    )
    (net (code "39") (name "Net-(C45-Pad1)") (class "Default")
      (node (ref "C45") (pin "1") (pinfunction "1_1") (pintype "passive"))
      (node (ref "C46") (pin "2") (pinfunction "2_2") (pintype "passive"))
      (node (ref "C47") (pin "2") (pinfunction "2_2") (pintype "passive"))
      (node (ref "L10") (pin "2") (pinfunction "2_2") (pintype "passive"))
      (node (ref "L11") (pin "1") (pinfunction "1_1") (pintype "passive"))
    )
    (net (code "40") (name "Net-(C47-Pad1)") (class "Default")
      (node (ref "C47") (pin "1") (pinfunction "1_1") (pintype "passive"))
      (node (ref "C48") (pin "2") (pinfunction "2_2") (pintype "passive"))
      (node (ref "C49") (pin "2") (pinfunction "2_2") (pintype "passive"))
      (node (ref "L11") (pin "2") (pinfunction "2_2") (pintype "passive"))
      (node (ref "L12") (pin "1") (pinfunction "1_1") (pintype "passive"))
    )
    (net (code "41") (name "Net-(C49-Pad1)") (class "Default")
      (node (ref "C49") (pin "1") (pinfunction "1_1") (pintype "passive"))
      (node (ref "C50") (pin "2") (pinfunction "2_2") (pintype "passive"))
      (node (ref "L12") (pin "2") (pinfunction "2_2") (pintype "passive"))
      (node (ref "R26") (pin "2") (pinfunction "2_2") (pintype "passive"))
      (node (ref "R27") (pin "1") (pinfunction "1_1") (pintype "passive"))
    )
    (net (code "42") (name "Net-(IC2-LX)") (class "Default")
      (node (ref "IC2") (pin "5") (pinfunction "LX_5") (pintype "bidirectional"))
      (node (ref "L3") (pin "1") (pinfunction "1_1") (pintype "passive"))
    )
    (net (code "43") (name "Net-(IC3-AVDD)") (class "Default")
      (node (ref "C8") (pin "1") (pinfunction "1_1") (pintype "passive"))
      (node (ref "IC3") (pin "A7") (pinfunction "AVDD_A7") (pintype "bidirectional"))
      (node (ref "L5") (pin "2") (pinfunction "2_2") (pintype "passive"))
    )
    (net (code "44") (name "Net-(IC3-CVDDQ)") (class "Default")
      (node (ref "C10") (pin "1") (pinfunction "1_1") (pintype "passive"))
      (node (ref "IC3") (pin "B6") (pinfunction "CVDDQ_B6") (pintype "bidirectional"))
      (node (ref "L7") (pin "2") (pinfunction "2_2") (pintype "passive"))
    )
    (net (code "45") (name "Net-(IC3-FSLC[0])") (class "Default")
      (node (ref "IC3") (pin "B2") (pinfunction "FSLC[0]_B2") (pintype "bidirectional"))
      (node (ref "IC3") (pin "B4") (pinfunction "FSLC[1]_B4") (pintype "bidirectional"))
      (node (ref "IC3") (pin "E6") (pinfunction "FSLC[2]_E6") (pintype "bidirectional"))
      (node (ref "R5") (pin "2") (pinfunction "2_2") (pintype "passive"))
    )
    (net (code "46") (name "Net-(IC3-GPIO[16])") (class "Default")
      (node (ref "IC3") (pin "J6") (pinfunction "GPIO[16]_J6") (pintype "bidirectional"))
      (node (ref "R12") (pin "2") (pinfunction "2_2") (pintype "passive"))
    )
    (net (code "47") (name "Net-(IC3-GPIO[22])") (class "Default")
      (node (ref "IC3") (pin "G6") (pinfunction "GPIO[22]_G6") (pintype "bidirectional"))
      (node (ref "R24") (pin "1") (pinfunction "1_1") (pintype "passive"))
    )
    (net (code "48") (name "Net-(IC3-GPIO[23])") (class "Default")
      (node (ref "IC3") (pin "K6") (pinfunction "GPIO[23]_K6") (pintype "bidirectional"))
      (node (ref "R4") (pin "1") (pinfunction "1_1") (pintype "passive"))
    )
    (net (code "49") (name "Net-(IC3-GPIO[25])") (class "Default")
      (node (ref "IC3") (pin "G5") (pinfunction "GPIO[25]_G5") (pintype "bidirectional"))
      (node (ref "R9") (pin "2") (pinfunction "2_2") (pintype "passive"))
    )
    (net (code "50") (name "Net-(IC3-GPIO[28])") (class "Default")
      (node (ref "IC3") (pin "J5") (pinfunction "GPIO[28]_J5") (pintype "bidirectional"))
      (node (ref "R11") (pin "2") (pinfunction "2_2") (pintype "passive"))
    )
    (net (code "51") (name "Net-(IC3-GPIO[29])") (class "Default")
      (node (ref "IC3") (pin "H5") (pinfunction "GPIO[29]_H5") (pintype "bidirectional"))
      (node (ref "R10") (pin "2") (pinfunction "2_2") (pintype "passive"))
    )
    (net (code "52") (name "Net-(IC3-GPIO[34])") (class "Default")
      (node (ref "IC3") (pin "J4") (pinfunction "GPIO[34]_J4") (pintype "bidirectional"))
      (node (ref "R2") (pin "1") (pinfunction "1_1") (pintype "passive"))
    )
    (net (code "53") (name "Net-(IC3-GPIO[35])") (class "Default")
      (node (ref "IC3") (pin "K1") (pinfunction "GPIO[35]_K1") (pintype "bidirectional"))
      (node (ref "R25") (pin "1") (pinfunction "1_1") (pintype "passive"))
    )
    (net (code "54") (name "Net-(IC3-GPIO[52])") (class "Default")
      (node (ref "IC3") (pin "D3") (pinfunction "GPIO[52]_D3") (pintype "bidirectional"))
      (node (ref "IC3") (pin "D4") (pinfunction "GPIO[53]_D4") (pintype "bidirectional"))
      (node (ref "R22") (pin "2") (pinfunction "2_2") (pintype "passive"))
    )
    (net (code "55") (name "Net-(IC3-R_USB2)") (class "Default")
      (node (ref "IC3") (pin "C8") (pinfunction "R_USB2_C8") (pintype "bidirectional"))
      (node (ref "R3") (pin "2") (pinfunction "2_2") (pintype "passive"))
    )
    (net (code "56") (name "Net-(IC3-R_USB3)") (class "Default")
      (node (ref "IC3") (pin "B3") (pinfunction "R_USB3_B3") (pintype "bidirectional"))
      (node (ref "R1") (pin "2") (pinfunction "2_2") (pintype "passive"))
    )
    (net (code "57") (name "Net-(IC3-SSTXM)") (class "Default")
      (node (ref "C13") (pin "1") (pinfunction "1_1") (pintype "passive"))
      (node (ref "IC3") (pin "A6") (pinfunction "SSTXM_A6") (pintype "bidirectional"))
    )
    (net (code "58") (name "Net-(IC3-SSTXP)") (class "Default")
      (node (ref "C12") (pin "1") (pinfunction "1_1") (pintype "passive"))
      (node (ref "IC3") (pin "A5") (pinfunction "SSTXP_A5") (pintype "bidirectional"))
    )
    (net (code "59") (name "Net-(IC3-U3RXVDDQ)") (class "Default")
      (node (ref "C7") (pin "1") (pinfunction "1_1") (pintype "passive"))
      (node (ref "IC3") (pin "A2") (pinfunction "U3RXVDDQ_A2") (pintype "bidirectional"))
      (node (ref "L4") (pin "2") (pinfunction "2_2") (pintype "passive"))
    )
    (net (code "60") (name "Net-(IC3-U3TXVDDQ)") (class "Default")
      (node (ref "C9") (pin "1") (pinfunction "1_1") (pintype "passive"))
      (node (ref "IC3") (pin "B5") (pinfunction "U3TXVDDQ_B5") (pintype "bidirectional"))
      (node (ref "L6") (pin "2") (pinfunction "2_2") (pintype "passive"))
    )
    (net (code "61") (name "Net-(IC3-XTALIN)") (class "Default")
      (node (ref "C6") (pin "2") (pinfunction "2_2") (pintype "passive"))
      (node (ref "IC3") (pin "C6") (pinfunction "XTALIN_C6") (pintype "bidirectional"))
      (node (ref "Y1") (pin "3") (pinfunction "XTAL_2_3") (pintype "bidirectional"))
    )
    (net (code "62") (name "Net-(IC3-XTALOUT)") (class "Default")
      (node (ref "C3") (pin "2") (pinfunction "2_2") (pintype "passive"))
      (node (ref "IC3") (pin "C7") (pinfunction "XTALOUT_C7") (pintype "bidirectional"))
      (node (ref "Y1") (pin "1") (pinfunction "XTAL_1_1") (pintype "bidirectional"))
    )
    (net (code "63") (name "Net-(IC5-AIN+)") (class "Default")
      (node (ref "IC5") (pin "8") (pinfunction "AIN+_8") (pintype "bidirectional"))
      (node (ref "R17") (pin "1") (pinfunction "1_1") (pintype "passive"))
    )
    (net (code "64") (name "Net-(IC5-AIN-)") (class "Default")
      (node (ref "IC5") (pin "9") (pinfunction "AIN-_9") (pintype "bidirectional"))
      (node (ref "R18") (pin "1") (pinfunction "1_1") (pintype "passive"))
    )
    (net (code "65") (name "Net-(IC5-D8+_{slash}DA0)") (class "Default")
      (node (ref "IC5") (pin "42") (pinfunction "D8+_/DA0_42") (pintype "bidirectional"))
      (node (ref "RN1") (pin "10") (pinfunction "10_10") (pintype "bidirectional"))
    )
    (net (code "66") (name "Net-(IC5-D9+_{slash}DA2)") (class "Default")
      (node (ref "IC5") (pin "44") (pinfunction "D9+_/DA2_44") (pintype "bidirectional"))
      (node (ref "RN1") (pin "15") (pinfunction "15_15") (pintype "bidirectional"))
    )
    (net (code "67") (name "Net-(IC5-D9-_{slash}DA1)") (class "Default")
      (node (ref "IC5") (pin "43") (pinfunction "D9-_/DA1_43") (pintype "bidirectional"))
      (node (ref "RN1") (pin "16") (pinfunction "16_16") (pintype "bidirectional"))
    )
    (net (code "68") (name "Net-(IC5-D10+_{slash}DA4)") (class "Default")
      (node (ref "IC5") (pin "46") (pinfunction "D10+_/DA4_46") (pintype "bidirectional"))
      (node (ref "RN1") (pin "13") (pinfunction "13_13") (pintype "bidirectional"))
    )
    (net (code "69") (name "Net-(IC5-D10-{slash}DA3)") (class "Default")
      (node (ref "IC5") (pin "45") (pinfunction "D10-/DA3_45") (pintype "bidirectional"))
      (node (ref "RN1") (pin "14") (pinfunction "14_14") (pintype "bidirectional"))
    )
    (net (code "70") (name "Net-(IC5-D11+_{slash}DA6)") (class "Default")
      (node (ref "IC5") (pin "48") (pinfunction "D11+_/DA6_48") (pintype "bidirectional"))
      (node (ref "RN1") (pin "11") (pinfunction "11_11") (pintype "bidirectional"))
    )
    (net (code "71") (name "Net-(IC5-D11-_{slash}DA5)") (class "Default")
      (node (ref "IC5") (pin "47") (pinfunction "D11-_/DA5_47") (pintype "bidirectional"))
      (node (ref "RN1") (pin "12") (pinfunction "12_12") (pintype "bidirectional"))
    )
    (net (code "72") (name "Net-(IC5-D12+{slash}DA8)") (class "Default")
      (node (ref "IC5") (pin "52") (pinfunction "D12+/DA8_52") (pintype "bidirectional"))
      (node (ref "RN2") (pin "10") (pinfunction "10_10") (pintype "bidirectional"))
    )
    (net (code "73") (name "Net-(IC5-D12-{slash}DA7)") (class "Default")
      (node (ref "IC5") (pin "51") (pinfunction "D12-/DA7_51") (pintype "bidirectional"))
      (node (ref "RN1") (pin "9") (pinfunction "9_9") (pintype "bidirectional"))
    )
    (net (code "74") (name "Net-(IC5-D13+{slash}DA10)") (class "Default")
      (node (ref "IC5") (pin "54") (pinfunction "D13+/DA10_54") (pintype "bidirectional"))
      (node (ref "RN2") (pin "15") (pinfunction "15_15") (pintype "bidirectional"))
    )
    (net (code "75") (name "Net-(IC5-D13-{slash}DA9)") (class "Default")
      (node (ref "IC5") (pin "53") (pinfunction "D13-/DA9_53") (pintype "bidirectional"))
      (node (ref "RN2") (pin "16") (pinfunction "16_16") (pintype "bidirectional"))
    )
    (net (code "76") (name "Net-(IC5-D14+{slash}DA12)") (class "Default")
      (node (ref "IC5") (pin "56") (pinfunction "D14+/DA12_56") (pintype "bidirectional"))
      (node (ref "RN2") (pin "13") (pinfunction "13_13") (pintype "bidirectional"))
    )
    (net (code "77") (name "Net-(IC5-D14-{slash}DA11)") (class "Default")
      (node (ref "IC5") (pin "55") (pinfunction "D14-/DA11_55") (pintype "bidirectional"))
      (node (ref "RN2") (pin "14") (pinfunction "14_14") (pintype "bidirectional"))
    )
    (net (code "78") (name "Net-(IC5-D15+{slash}DA14)") (class "Default")
      (node (ref "IC5") (pin "58") (pinfunction "D15+/DA14_58") (pintype "bidirectional"))
      (node (ref "RN2") (pin "11") (pinfunction "11_11") (pintype "bidirectional"))
    )
    (net (code "79") (name "Net-(IC5-D15-{slash}DA13)") (class "Default")
      (node (ref "IC5") (pin "57") (pinfunction "D15-/DA13_57") (pintype "bidirectional"))
      (node (ref "RN2") (pin "12") (pinfunction "12_12") (pintype "bidirectional"))
    )
    (net (code "80") (name "Net-(IC5-MODE)") (class "Default")
      (node (ref "IC5") (pin "62") (pinfunction "MODE_62") (pintype "bidirectional"))
      (node (ref "R13") (pin "1") (pinfunction "1_1") (pintype "passive"))
      (node (ref "R14") (pin "1") (pinfunction "1_1") (pintype "passive"))
    )
    (net (code "81") (name "Net-(IC5-OF-{slash}DA15)") (class "Default")
      (node (ref "IC5") (pin "59") (pinfunction "OF-/DA15_59") (pintype "bidirectional"))
      (node (ref "RN2") (pin "9") (pinfunction "9_9") (pintype "bidirectional"))
    )
    (net (code "82") (name "Net-(IC5-RAND)") (class "Default")
      (node (ref "IC5") (pin "63") (pinfunction "RAND_63") (pintype "bidirectional"))
      (node (ref "R15") (pin "1") (pinfunction "1_1") (pintype "passive"))
      (node (ref "R16") (pin "1") (pinfunction "1_1") (pintype "passive"))
    )
    (net (code "83") (name "Net-(IC6-+IN_1)") (class "Default")
      (node (ref "C41") (pin "1") (pinfunction "1_1") (pintype "passive"))
      (node (ref "IC6") (pin "13") (pinfunction "+IN_1_13") (pintype "bidirectional"))
      (node (ref "IC6") (pin "14") (pinfunction "+IN_2_14") (pintype "bidirectional"))
    )
    (net (code "84") (name "Net-(IC6-+OUT)") (class "Default")
      (node (ref "IC6") (pin "8") (pinfunction "+OUT_8") (pintype "bidirectional"))
      (node (ref "R17") (pin "2") (pinfunction "2_2") (pintype "passive"))
    )
    (net (code "85") (name "Net-(IC6--IN_1)") (class "Default")
      (node (ref "C40") (pin "1") (pinfunction "1_1") (pintype "passive"))
      (node (ref "IC6") (pin "15") (pinfunction "-IN_1_15") (pintype "bidirectional"))
      (node (ref "IC6") (pin "16") (pinfunction "-IN_2_16") (pintype "bidirectional"))
    )
    (net (code "86") (name "Net-(IC6--OUT)") (class "Default")
      (node (ref "IC6") (pin "5") (pinfunction "-OUT_5") (pintype "bidirectional"))
      (node (ref "R18") (pin "2") (pinfunction "2_2") (pintype "passive"))
    )
    (net (code "87") (name "Net-(IC7-CLK0)") (class "Default")
      (node (ref "C51") (pin "2") (pinfunction "2_2") (pintype "passive"))
      (node (ref "IC7") (pin "10") (pinfunction "CLK0_10") (pintype "bidirectional"))
    )
    (net (code "88") (name "Net-(IC7-XA)") (class "Default")
      (node (ref "C37") (pin "2") (pinfunction "2_2") (pintype "passive"))
      (node (ref "IC7") (pin "2") (pinfunction "XA_2") (pintype "bidirectional"))
      (node (ref "Y2") (pin "3") (pinfunction "XTAL_2_3") (pintype "bidirectional"))
    )
    (net (code "89") (name "Net-(IC7-XB)") (class "Default")
      (node (ref "C34") (pin "2") (pinfunction "2_2") (pintype "passive"))
      (node (ref "IC7") (pin "3") (pinfunction "XB_3") (pintype "bidirectional"))
      (node (ref "Y2") (pin "1") (pinfunction "XTAL_1_1") (pintype "bidirectional"))
    )
    (net (code "90") (name "Net-(IC8-D)") (class "Default")
      (node (ref "C51") (pin "1") (pinfunction "1_1") (pintype "passive"))
      (node (ref "IC8") (pin "5") (pinfunction "D_5") (pintype "bidirectional"))
      (node (ref "R23") (pin "1") (pinfunction "1_1") (pintype "passive"))
    )
    (net (code "91") (name "Net-(J1-SHIELD-PadSH1)") (class "Default")
      (node (ref "J1") (pin "SH1") (pinfunction "SHIELD_SH1") (pintype "power_in"))
      (node (ref "J1") (pin "SH2") (pinfunction "SHIELD_SH2") (pintype "power_in"))
      (node (ref "L1") (pin "2") (pinfunction "2_2") (pintype "passive"))
    )
    (net (code "92") (name "Net-(J1-VBUS)") (class "Default")
      (node (ref "J1") (pin "1") (pinfunction "VBUS_1") (pintype "power_in"))
      (node (ref "L2") (pin "2") (pinfunction "2_2") (pintype "passive"))
    )
    (net (code "93") (name "Net-(R26-Pad1)") (class "Default")
      (node (ref "R26") (pin "1") (pinfunction "1_1") (pintype "passive"))
      (node (ref "R28") (pin "1") (pinfunction "1_1") (pintype "passive"))
      (node (ref "X1") (pin "1") (pinfunction "1_1") (pintype "passive"))
    )
    (net (code "94") (name "PCLK") (class "Default")
      (node (ref "IC5") (pin "41") (pinfunction "D8-/CLKOUTA_41") (pintype "bidirectional"))
      (node (ref "R12") (pin "1") (pinfunction "1_1") (pintype "passive"))
    )
    (net (code "95") (name "PLL_LD") (class "Default")
      (node (ref "R25") (pin "2") (pinfunction "2_2") (pintype "passive"))
      (node (ref "SV1") (pin "6") (pinfunction "6_6") (pintype "passive"))
    )
    (net (code "96") (name "SSD1_N") (class "Default")
      (node (ref "D2") (pin "6") (pinfunction "I/O1_6") (pintype "bidirectional"))
      (node (ref "IC3") (pin "A10") (pinfunction "DM_A10") (pintype "bidirectional"))
    )
    (net (code "97") (name "SSD1_P") (class "Default")
      (node (ref "D2") (pin "4") (pinfunction "I/O2_4") (pintype "bidirectional"))
      (node (ref "IC3") (pin "A9") (pinfunction "DP_A9") (pintype "bidirectional"))
    )
    (net (code "98") (name "SSD_N") (class "Default")
      (node (ref "D2") (pin "1") (pinfunction "I/O1_2_1") (pintype "bidirectional"))
      (node (ref "J1") (pin "2") (pinfunction "D-_2") (pintype "bidirectional"))
    )
    (net (code "99") (name "SSD_P") (class "Default")
      (node (ref "D2") (pin "3") (pinfunction "I/O2_2_3") (pintype "bidirectional"))
      (node (ref "J1") (pin "3") (pinfunction "D+_3") (pintype "bidirectional"))
    )
    (net (code "100") (name "SS_RX_N") (class "Default")
      (node (ref "D1") (pin "4") (pinfunction "4_4") (pintype "bidirectional"))
      (node (ref "D1") (pin "7") (pinfunction "7_7") (pintype "bidirectional"))
      (node (ref "IC3") (pin "A3") (pinfunction "SSRXM_A3") (pintype "bidirectional"))
      (node (ref "J1") (pin "9") (pinfunction "STDA_SSTX-/STDB_SSRX-_9") (pintype "bidirectional"))
    )
    (net (code "101") (name "SS_RX_P") (class "Default")
      (node (ref "D1") (pin "5") (pinfunction "5_5") (pintype "bidirectional"))
      (node (ref "D1") (pin "6") (pinfunction "6_6") (pintype "bidirectional"))
      (node (ref "IC3") (pin "A4") (pinfunction "SSRXP_A4") (pintype "bidirectional"))
      (node (ref "J1") (pin "10") (pinfunction "STDA_SSTX+/STDB_SSRX+_10") (pintype "bidirectional"))
    )
    (net (code "102") (name "SS_TX_N") (class "Default")
      (node (ref "C13") (pin "2") (pinfunction "2_2") (pintype "passive"))
      (node (ref "D1") (pin "1") (pinfunction "1_1") (pintype "bidirectional"))
      (node (ref "D1") (pin "10") (pinfunction "10_10") (pintype "bidirectional"))
      (node (ref "J1") (pin "6") (pinfunction "STDA_SSRX-/STDB_SSTX-_6") (pintype "bidirectional"))
    )
    (net (code "103") (name "SS_TX_P") (class "Default")
      (node (ref "C12") (pin "2") (pinfunction "2_2") (pintype "passive"))
      (node (ref "D1") (pin "2") (pinfunction "2_2") (pintype "bidirectional"))
      (node (ref "D1") (pin "9") (pinfunction "9_9") (pintype "bidirectional"))
      (node (ref "J1") (pin "7") (pinfunction "STDA_SSRX+/STDB_SSTX+_7") (pintype "bidirectional"))
    )
    (net (code "104") (name "VBUS") (class "Default")
      (node (ref "D2") (pin "5") (pinfunction "VBUS_5") (pintype "power_in"))
    )
    (net (code "105") (name "VCM") (class "Default")
      (node (ref "C36") (pin "2") (pinfunction "2_2") (pintype "passive"))
      (node (ref "IC5") (pin "3") (pinfunction "VCM_3") (pintype "bidirectional"))
      (node (ref "IC6") (pin "2") (pinfunction "VOCM_2") (pintype "bidirectional"))
    )
    (net (code "106") (name "VPROR") (class "Default")
      (node (ref "C32") (pin "2") (pinfunction "2_2") (pintype "passive"))
      (node (ref "C33") (pin "2") (pinfunction "2_2") (pintype "passive"))
      (node (ref "C35") (pin "2") (pinfunction "2_2") (pintype "passive"))
      (node (ref "C38") (pin "2") (pinfunction "2_2") (pintype "passive"))
      (node (ref "IC6") (pin "1") (pinfunction "V+_1_1") (pintype "bidirectional"))
      (node (ref "IC6") (pin "10") (pinfunction "V+_3_10") (pintype "bidirectional"))
      (node (ref "IC6") (pin "3") (pinfunction "V+_2_3") (pintype "bidirectional"))
      (node (ref "L8") (pin "2") (pinfunction "2_2") (pintype "passive"))
      (node (ref "L9") (pin "2") (pinfunction "2_2") (pintype "passive"))
    )
    (net (code "107") (name "VUSB") (class "Default")
      (node (ref "C1") (pin "2") (pinfunction "2_2") (pintype "passive"))
      (node (ref "C11") (pin "1") (pinfunction "1_1") (pintype "passive"))
      (node (ref "C2") (pin "2") (pinfunction "2_2") (pintype "passive"))
      (node (ref "C23") (pin "2") (pinfunction "2_2") (pintype "passive"))
      (node (ref "IC1") (pin "3") (pinfunction "IN_3") (pintype "input"))
      (node (ref "IC2") (pin "1") (pinfunction "VIN_1") (pintype "bidirectional"))
      (node (ref "IC2") (pin "3") (pinfunction "EN_3") (pintype "bidirectional"))
      (node (ref "IC3") (pin "E11") (pinfunction "VBUS_E11") (pintype "bidirectional"))
      (node (ref "IC4") (pin "3") (pinfunction "IN_3") (pintype "input"))
      (node (ref "L2") (pin "1") (pinfunction "1_1") (pintype "passive"))
      (node (ref "SV1") (pin "1") (pinfunction "1_1") (pintype "passive"))
      (node (ref "SV1") (pin "2") (pinfunction "2_2") (pintype "passive"))
    )
    (net (code "108") (name "unconnected-(IC3-CLKIN-PadD7)") (class "Default")
      (node (ref "IC3") (pin "D7") (pinfunction "CLKIN_D7") (pintype "bidirectional"))
    )
    (net (code "109") (name "unconnected-(IC3-CLKIN_32-PadD6)") (class "Default")
      (node (ref "IC3") (pin "D6") (pinfunction "CLKIN_32_D6") (pintype "bidirectional"))
    )
    (net (code "110") (name "unconnected-(IC3-GPIO[17]-PadK8)") (class "Default")
      (node (ref "IC3") (pin "K8") (pinfunction "GPIO[17]_K8") (pintype "bidirectional"))
    )
    (net (code "111") (name "unconnected-(IC3-GPIO[18]-PadK7)") (class "Default")
      (node (ref "IC3") (pin "K7") (pinfunction "GPIO[18]_K7") (pintype "bidirectional"))
    )
    (net (code "112") (name "unconnected-(IC3-GPIO[19]-PadJ7)") (class "Default")
      (node (ref "IC3") (pin "J7") (pinfunction "GPIO[19]_J7") (pintype "bidirectional"))
    )
    (net (code "113") (name "unconnected-(IC3-GPIO[20]-PadH7)") (class "Default")
      (node (ref "IC3") (pin "H7") (pinfunction "GPIO[20]_H7") (pintype "bidirectional"))
    )
    (net (code "114") (name "unconnected-(IC3-GPIO[21]-PadG7)") (class "Default")
      (node (ref "IC3") (pin "G7") (pinfunction "GPIO[21]_G7") (pintype "bidirectional"))
    )
    (net (code "115") (name "unconnected-(IC3-GPIO[24]-PadH8)") (class "Default")
      (node (ref "IC3") (pin "H8") (pinfunction "GPIO[24]_H8") (pintype "bidirectional"))
    )
    (net (code "116") (name "unconnected-(IC3-GPIO[26]-PadH6)") (class "Default")
      (node (ref "IC3") (pin "H6") (pinfunction "GPIO[26]_H6") (pintype "bidirectional"))
    )
    (net (code "117") (name "unconnected-(IC3-GPIO[27]-PadK5)") (class "Default")
      (node (ref "IC3") (pin "K5") (pinfunction "GPIO[27]_K5") (pintype "bidirectional"))
    )
    (net (code "118") (name "unconnected-(IC3-GPIO[33]-PadK2)") (class "Default")
      (node (ref "IC3") (pin "K2") (pinfunction "GPIO[33]_K2") (pintype "bidirectional"))
    )
    (net (code "119") (name "unconnected-(IC3-GPIO[36]-PadJ2)") (class "Default")
      (node (ref "IC3") (pin "J2") (pinfunction "GPIO[36]_J2") (pintype "bidirectional"))
    )
    (net (code "120") (name "unconnected-(IC3-GPIO[37]-PadJ3)") (class "Default")
      (node (ref "IC3") (pin "J3") (pinfunction "GPIO[37]_J3") (pintype "bidirectional"))
    )
    (net (code "121") (name "unconnected-(IC3-GPIO[38]-PadJ1)") (class "Default")
      (node (ref "IC3") (pin "J1") (pinfunction "GPIO[38]_J1") (pintype "bidirectional"))
    )
    (net (code "122") (name "unconnected-(IC3-GPIO[39]-PadH2)") (class "Default")
      (node (ref "IC3") (pin "H2") (pinfunction "GPIO[39]_H2") (pintype "bidirectional"))
    )
    (net (code "123") (name "unconnected-(IC3-GPIO[40]-PadH3)") (class "Default")
      (node (ref "IC3") (pin "H3") (pinfunction "GPIO[40]_H3") (pintype "bidirectional"))
    )
    (net (code "124") (name "unconnected-(IC3-GPIO[41]-PadF4)") (class "Default")
      (node (ref "IC3") (pin "F4") (pinfunction "GPIO[41]_F4") (pintype "bidirectional"))
    )
    (net (code "125") (name "unconnected-(IC3-GPIO[42]-PadG2)") (class "Default")
      (node (ref "IC3") (pin "G2") (pinfunction "GPIO[42]_G2") (pintype "bidirectional"))
    )
    (net (code "126") (name "unconnected-(IC3-GPIO[43]-PadG3)") (class "Default")
      (node (ref "IC3") (pin "G3") (pinfunction "GPIO[43]_G3") (pintype "bidirectional"))
    )
    (net (code "127") (name "unconnected-(IC3-GPIO[44]-PadF3)") (class "Default")
      (node (ref "IC3") (pin "F3") (pinfunction "GPIO[44]_F3") (pintype "bidirectional"))
    )
    (net (code "128") (name "unconnected-(IC3-GPIO[45]-PadF2)") (class "Default")
      (node (ref "IC3") (pin "F2") (pinfunction "GPIO[45]_F2") (pintype "bidirectional"))
    )
    (net (code "129") (name "unconnected-(IC3-GPIO[46]-PadF5)") (class "Default")
      (node (ref "IC3") (pin "F5") (pinfunction "GPIO[46]_F5") (pintype "bidirectional"))
    )
    (net (code "130") (name "unconnected-(IC3-GPIO[47]-PadE1)") (class "Default")
      (node (ref "IC3") (pin "E1") (pinfunction "GPIO[47]_E1") (pintype "bidirectional"))
    )
    (net (code "131") (name "unconnected-(IC3-GPIO[48]-PadE5)") (class "Default")
      (node (ref "IC3") (pin "E5") (pinfunction "GPIO[48]_E5") (pintype "bidirectional"))
    )
    (net (code "132") (name "unconnected-(IC3-GPIO[49]-PadE4)") (class "Default")
      (node (ref "IC3") (pin "E4") (pinfunction "GPIO[49]_E4") (pintype "bidirectional"))
    )
    (net (code "133") (name "unconnected-(IC3-GPIO[50]-PadD1)") (class "Default")
      (node (ref "IC3") (pin "D1") (pinfunction "GPIO[50]_D1") (pintype "bidirectional"))
    )
    (net (code "134") (name "unconnected-(IC3-GPIO[51]-PadD2)") (class "Default")
      (node (ref "IC3") (pin "D2") (pinfunction "GPIO[51]_D2") (pintype "bidirectional"))
    )
    (net (code "135") (name "unconnected-(IC3-GPIO[54]-PadC1)") (class "Default")
      (node (ref "IC3") (pin "C1") (pinfunction "GPIO[54]_C1") (pintype "bidirectional"))
    )
    (net (code "136") (name "unconnected-(IC3-GPIO[55]-PadC2)") (class "Default")
      (node (ref "IC3") (pin "C2") (pinfunction "GPIO[55]_C2") (pintype "bidirectional"))
    )
    (net (code "137") (name "unconnected-(IC3-GPIO[56]-PadD5)") (class "Default")
      (node (ref "IC3") (pin "D5") (pinfunction "GPIO[56]_D5") (pintype "bidirectional"))
    )
    (net (code "138") (name "unconnected-(IC3-GPIO[57]-PadC4)") (class "Default")
      (node (ref "IC3") (pin "C4") (pinfunction "GPIO[57]_C4") (pintype "bidirectional"))
    )
    (net (code "139") (name "unconnected-(IC3-INT#-PadL8)") (class "Default")
      (node (ref "IC3") (pin "L8") (pinfunction "INT#_L8") (pintype "bidirectional"))
    )
    (net (code "140") (name "unconnected-(IC3-NC-PadA11)") (class "Default")
      (node (ref "IC3") (pin "A11") (pinfunction "NC_A11") (pintype "no_connect"))
    )
    (net (code "141") (name "unconnected-(IC3-OTG_ID-PadC9)") (class "Default")
      (node (ref "IC3") (pin "C9") (pinfunction "OTG_ID_C9") (pintype "bidirectional"))
    )
    (net (code "142") (name "unconnected-(IC3-O[60]-PadD11)") (class "Default")
      (node (ref "IC3") (pin "D11") (pinfunction "O[60]_D11") (pintype "bidirectional"))
    )
    (net (code "143") (name "unconnected-(IC3-TCK-PadF6)") (class "Default")
      (node (ref "IC3") (pin "F6") (pinfunction "TCK_F6") (pintype "bidirectional"))
    )
    (net (code "144") (name "unconnected-(IC3-TDI-PadE7)") (class "Default")
      (node (ref "IC3") (pin "E7") (pinfunction "TDI_E7") (pintype "bidirectional"))
    )
    (net (code "145") (name "unconnected-(IC3-TDO-PadC10)") (class "Default")
      (node (ref "IC3") (pin "C10") (pinfunction "TDO_C10") (pintype "bidirectional"))
    )
    (net (code "146") (name "unconnected-(IC3-TMS-PadE8)") (class "Default")
      (node (ref "IC3") (pin "E8") (pinfunction "TMS_E8") (pintype "bidirectional"))
    )
    (net (code "147") (name "unconnected-(IC3-TRST#-PadB11)") (class "Default")
      (node (ref "IC3") (pin "B11") (pinfunction "TRST#_B11") (pintype "bidirectional"))
    )
    (net (code "148") (name "unconnected-(IC3-VBATT-PadE10)") (class "Default")
      (node (ref "IC3") (pin "E10") (pinfunction "VBATT_E10") (pintype "bidirectional"))
    )
    (net (code "149") (name "unconnected-(IC5-CLKOUT+{slash}CLKOUTB-Pad40)") (class "Default")
      (node (ref "IC5") (pin "40") (pinfunction "CLKOUT+/CLKOUTB_40") (pintype "bidirectional"))
    )
    (net (code "150") (name "unconnected-(IC5-CLKOUT-_{slash}OFB-Pad39)") (class "Default")
      (node (ref "IC5") (pin "39") (pinfunction "CLKOUT-_/OFB_39") (pintype "bidirectional"))
    )
    (net (code "151") (name "unconnected-(IC5-D0-{slash}DB0-Pad21)") (class "Default")
      (node (ref "IC5") (pin "21") (pinfunction "D0-/DB0_21") (pintype "bidirectional"))
    )
    (net (code "152") (name "unconnected-(IC5-D1+{slash}DB3-Pad24)") (class "Default")
      (node (ref "IC5") (pin "24") (pinfunction "D1+/DB3_24") (pintype "bidirectional"))
    )
    (net (code "153") (name "unconnected-(IC5-D1-{slash}DB2-Pad23)") (class "Default")
      (node (ref "IC5") (pin "23") (pinfunction "D1-/DB2_23") (pintype "bidirectional"))
    )
    (net (code "154") (name "unconnected-(IC5-D2+{slash}DB5-Pad26)") (class "Default")
      (node (ref "IC5") (pin "26") (pinfunction "D2+/DB5_26") (pintype "bidirectional"))
    )
    (net (code "155") (name "unconnected-(IC5-D2-{slash}DB4-Pad25)") (class "Default")
      (node (ref "IC5") (pin "25") (pinfunction "D2-/DB4_25") (pintype "bidirectional"))
    )
    (net (code "156") (name "unconnected-(IC5-D3+{slash}DB7-Pad28)") (class "Default")
      (node (ref "IC5") (pin "28") (pinfunction "D3+/DB7_28") (pintype "bidirectional"))
    )
    (net (code "157") (name "unconnected-(IC5-D3-{slash}DB6-Pad27)") (class "Default")
      (node (ref "IC5") (pin "27") (pinfunction "D3-/DB6_27") (pintype "bidirectional"))
    )
    (net (code "158") (name "unconnected-(IC5-D4+{slash}DB9-Pad30)") (class "Default")
      (node (ref "IC5") (pin "30") (pinfunction "D4+/DB9_30") (pintype "bidirectional"))
    )
    (net (code "159") (name "unconnected-(IC5-D4-{slash}DB8-Pad29)") (class "Default")
      (node (ref "IC5") (pin "29") (pinfunction "D4-/DB8_29") (pintype "bidirectional"))
    )
    (net (code "160") (name "unconnected-(IC5-D5+_{slash}DB11-Pad34)") (class "Default")
      (node (ref "IC5") (pin "34") (pinfunction "D5+_/DB11_34") (pintype "bidirectional"))
    )
    (net (code "161") (name "unconnected-(IC5-D5-{slash}DB10-Pad33)") (class "Default")
      (node (ref "IC5") (pin "33") (pinfunction "D5-/DB10_33") (pintype "bidirectional"))
    )
    (net (code "162") (name "unconnected-(IC5-D6+{slash}DB13-Pad36)") (class "Default")
      (node (ref "IC5") (pin "36") (pinfunction "D6+/DB13_36") (pintype "bidirectional"))
    )
    (net (code "163") (name "unconnected-(IC5-D6-_{slash}DB12-Pad35)") (class "Default")
      (node (ref "IC5") (pin "35") (pinfunction "D6-_/DB12_35") (pintype "bidirectional"))
    )
    (net (code "164") (name "unconnected-(IC5-D7+_{slash}DB15-Pad38)") (class "Default")
      (node (ref "IC5") (pin "38") (pinfunction "D7+_/DB15_38") (pintype "bidirectional"))
    )
    (net (code "165") (name "unconnected-(IC5-D7-_{slash}DB14-Pad37)") (class "Default")
      (node (ref "IC5") (pin "37") (pinfunction "D7-_/DB14_37") (pintype "bidirectional"))
    )
    (net (code "166") (name "unconnected-(IC5-DO+{slash}DB1-Pad22)") (class "Default")
      (node (ref "IC5") (pin "22") (pinfunction "DO+/DB1_22") (pintype "bidirectional"))
    )
    (net (code "167") (name "unconnected-(IC5-NC-Pad64)") (class "Default")
      (node (ref "IC5") (pin "64") (pinfunction "NC_64") (pintype "no_connect"))
    )
    (net (code "168") (name "unconnected-(IC6-+OUTF-Pad7)") (class "Default")
      (node (ref "IC6") (pin "7") (pinfunction "+OUTF_7") (pintype "bidirectional"))
    )
    (net (code "169") (name "unconnected-(IC6--OUTF-Pad6)") (class "Default")
      (node (ref "IC6") (pin "6") (pinfunction "-OUTF_6") (pintype "bidirectional"))
    )
    (net (code "170") (name "unconnected-(IC7-CLK1-Pad9)") (class "Default")
      (node (ref "IC7") (pin "9") (pinfunction "CLK1_9") (pintype "bidirectional"))
    )
    (net (code "171") (name "unconnected-(IC7-CLK2-Pad6)") (class "Default")
      (node (ref "IC7") (pin "6") (pinfunction "CLK2_6") (pintype "bidirectional"))
    )
    (net (code "172") (name "unconnected-(J1-ID-Pad4)") (class "Default")
      (node (ref "J1") (pin "4") (pinfunction "ID_4") (pintype "bidirectional"))
    )
  )
)
